# PokerFaceTestBoard.net
KiCad netlist of a schematic drawn in Altium Designer
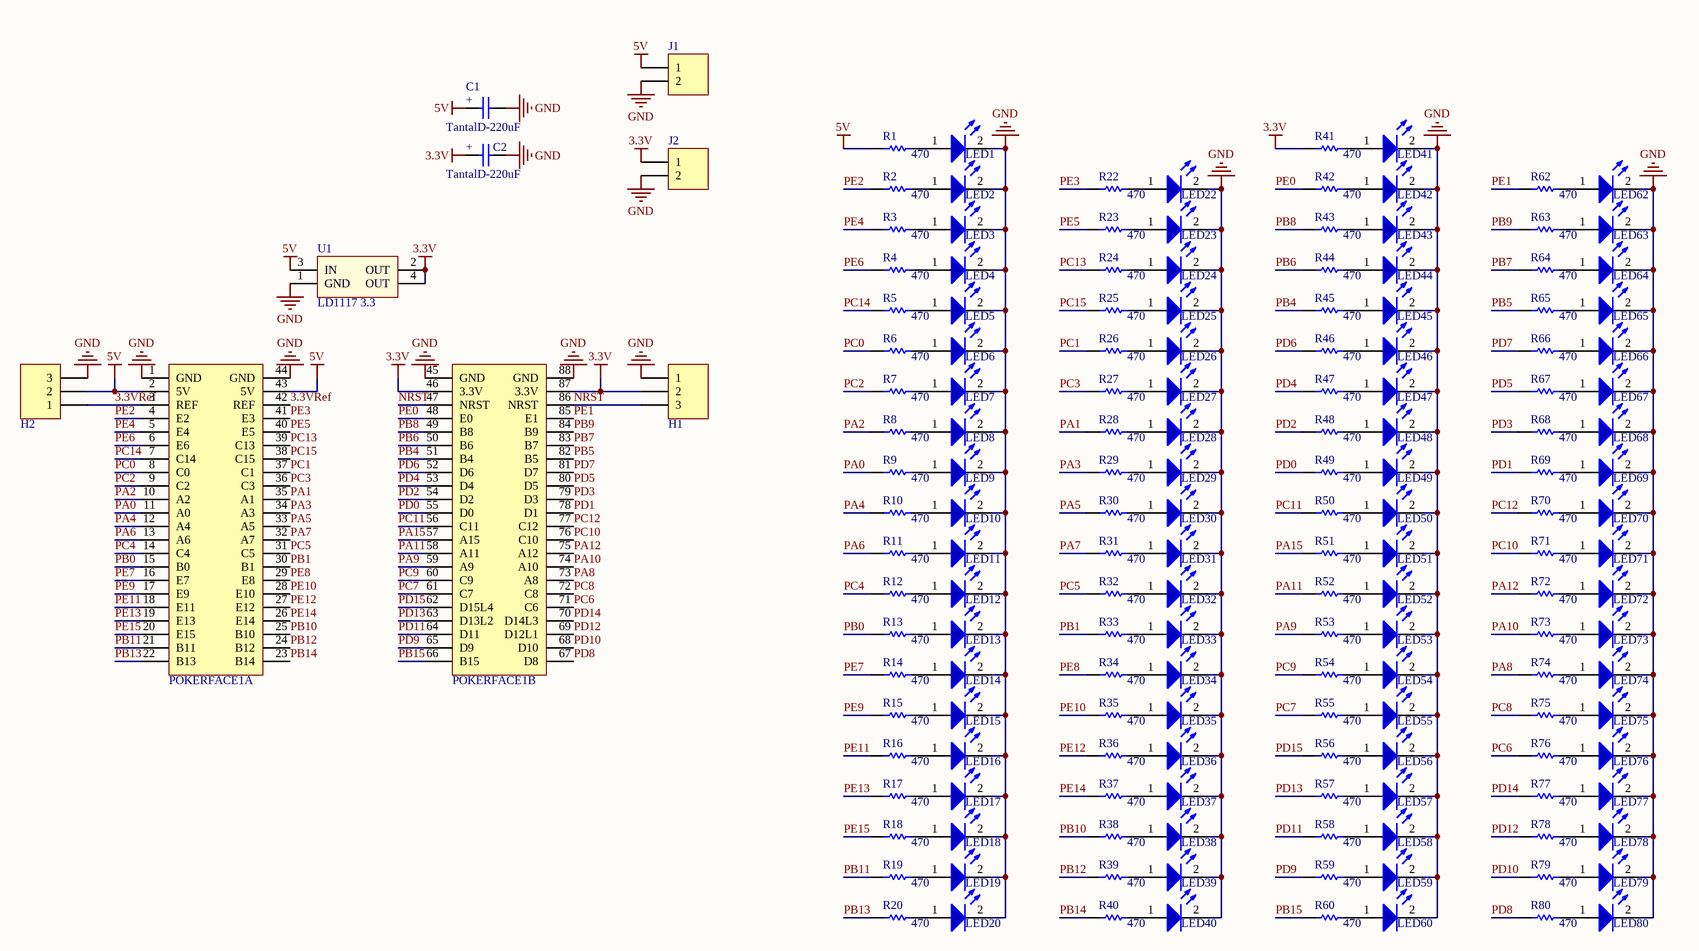
[diagram p0: PokerFaceTestBoard.SchDoc]

(export (version "E")
  (design (tool "Eeschema 10.0.6"))
  (components
    (comp (ref "C1")
      (value "TantalD-220uF")
      (footprint "MY_CAP_SMD-D")
      (description "7.3X4.3MM")
      (libsource (lib "AMINLIB") (part "CAP_TANTAL_D"))
    )
    (comp (ref "C2")
      (value "TantalD-220uF")
      (footprint "MY_CAP_SMD-D")
      (description "7.3X4.3MM")
      (libsource (lib "AMINLIB") (part "CAP_TANTAL_D"))
    )
    (comp (ref "H1")
      (value "WE-2.54 mm Pin Header & Jumper 61300311121")
      (footprint "61300311121")
      (description "WR-PHD 2.54mm Pin Header")
      (fields
        (field (name "MANUFACTURER") "Würth Elektronik eiSos GmbH")
        (field (name "PARTNO") "61300311121")
        (field (name "CREATED BY") "Karrer Zheng")
      )
      (libsource (lib "") (part "WE-2.54 mm Pin Header & Jumper 61300311121_1"))
    )
    (comp (ref "H2")
      (value "WE-2.54 mm Pin Header & Jumper 61300311121")
      (footprint "61300311121")
      (description "WR-PHD 2.54mm Pin Header")
      (fields
        (field (name "MANUFACTURER") "Würth Elektronik eiSos GmbH")
        (field (name "PARTNO") "61300311121")
        (field (name "CREATED BY") "Karrer Zheng")
      )
      (libsource (lib "WE_WR-PHD_Pin Header_2.54mm_rev15c") (part "WE-2.54 mm Pin Header & Jumper 61300311121"))
    )
    (comp (ref "J1")
      (value "691312510002")
      (footprint "691312510002")
      (description "WR-TBL Terminal Blocks Serie 312 – 5.08 mm")
      (fields
        (field (name "MANUFACTURER") "Würth Elektronik eiSos GmbH")
        (field (name "CREATED BY") "Karrer Zheng")
      )
      (libsource (lib "WE_WR-TBL_Pluggable System_5.08 mm_rev15b") (part "691312510002"))
    )
    (comp (ref "J2")
      (value "691312510002")
      (footprint "691312510002")
      (description "WR-TBL Terminal Blocks Serie 312 – 5.08 mm")
      (fields
        (field (name "MANUFACTURER") "Würth Elektronik eiSos GmbH")
        (field (name "CREATED BY") "Karrer Zheng")
      )
      (libsource (lib "WE_WR-TBL_Pluggable System_5.08 mm_rev15b") (part "691312510002"))
    )
    (comp (ref "LED1")
      (value "150080BS75000")
      (footprint "LED_0805_Blue")
      (description "SMD mono-color Chip LED, WL-SMCW, Blue")
      (fields
        (field (name "MANUFACTURER") "W黵th Elektronik eiSos GmbH")
        (field (name "CREATED BY") "Christin Otto")
      )
      (libsource (lib "WL-SMCW_rev15b1") (part "WL-SMCW 0805  150080BS75000"))
    )
    (comp (ref "LED2")
      (value "150080BS75000")
      (footprint "LED_0805_Blue")
      (description "SMD mono-color Chip LED, WL-SMCW, Blue")
      (fields
        (field (name "MANUFACTURER") "W黵th Elektronik eiSos GmbH")
        (field (name "CREATED BY") "Christin Otto")
      )
      (libsource (lib "WL-SMCW_rev15b1") (part "WL-SMCW 0805  150080BS75000"))
    )
    (comp (ref "LED3")
      (value "150080BS75000")
      (footprint "LED_0805_Blue")
      (description "SMD mono-color Chip LED, WL-SMCW, Blue")
      (fields
        (field (name "MANUFACTURER") "W黵th Elektronik eiSos GmbH")
        (field (name "CREATED BY") "Christin Otto")
      )
      (libsource (lib "WL-SMCW_rev15b1") (part "WL-SMCW 0805  150080BS75000"))
    )
    (comp (ref "LED4")
      (value "150080BS75000")
      (footprint "LED_0805_Blue")
      (description "SMD mono-color Chip LED, WL-SMCW, Blue")
      (fields
        (field (name "MANUFACTURER") "W黵th Elektronik eiSos GmbH")
        (field (name "CREATED BY") "Christin Otto")
      )
      (libsource (lib "WL-SMCW_rev15b1") (part "WL-SMCW 0805  150080BS75000"))
    )
    (comp (ref "LED5")
      (value "150080BS75000")
      (footprint "LED_0805_Blue")
      (description "SMD mono-color Chip LED, WL-SMCW, Blue")
      (fields
        (field (name "MANUFACTURER") "W黵th Elektronik eiSos GmbH")
        (field (name "CREATED BY") "Christin Otto")
      )
      (libsource (lib "WL-SMCW_rev15b1") (part "WL-SMCW 0805  150080BS75000"))
    )
    (comp (ref "LED6")
      (value "150080BS75000")
      (footprint "LED_0805_Blue")
      (description "SMD mono-color Chip LED, WL-SMCW, Blue")
      (fields
        (field (name "MANUFACTURER") "W黵th Elektronik eiSos GmbH")
        (field (name "CREATED BY") "Christin Otto")
      )
      (libsource (lib "WL-SMCW_rev15b1") (part "WL-SMCW 0805  150080BS75000"))
    )
    (comp (ref "LED7")
      (value "150080BS75000")
      (footprint "LED_0805_Blue")
      (description "SMD mono-color Chip LED, WL-SMCW, Blue")
      (fields
        (field (name "MANUFACTURER") "W黵th Elektronik eiSos GmbH")
        (field (name "CREATED BY") "Christin Otto")
      )
      (libsource (lib "WL-SMCW_rev15b1") (part "WL-SMCW 0805  150080BS75000"))
    )
    (comp (ref "LED8")
      (value "150080BS75000")
      (footprint "LED_0805_Blue")
      (description "SMD mono-color Chip LED, WL-SMCW, Blue")
      (fields
        (field (name "MANUFACTURER") "W黵th Elektronik eiSos GmbH")
        (field (name "CREATED BY") "Christin Otto")
      )
      (libsource (lib "WL-SMCW_rev15b1") (part "WL-SMCW 0805  150080BS75000"))
    )
    (comp (ref "LED9")
      (value "150080BS75000")
      (footprint "LED_0805_Blue")
      (description "SMD mono-color Chip LED, WL-SMCW, Blue")
      (fields
        (field (name "MANUFACTURER") "W黵th Elektronik eiSos GmbH")
        (field (name "CREATED BY") "Christin Otto")
      )
      (libsource (lib "WL-SMCW_rev15b1") (part "WL-SMCW 0805  150080BS75000"))
    )
    (comp (ref "LED10")
      (value "150080BS75000")
      (footprint "LED_0805_Blue")
      (description "SMD mono-color Chip LED, WL-SMCW, Blue")
      (fields
        (field (name "MANUFACTURER") "W黵th Elektronik eiSos GmbH")
        (field (name "CREATED BY") "Christin Otto")
      )
      (libsource (lib "WL-SMCW_rev15b1") (part "WL-SMCW 0805  150080BS75000"))
    )
    (comp (ref "LED11")
      (value "150080BS75000")
      (footprint "LED_0805_Blue")
      (description "SMD mono-color Chip LED, WL-SMCW, Blue")
      (fields
        (field (name "MANUFACTURER") "W黵th Elektronik eiSos GmbH")
        (field (name "CREATED BY") "Christin Otto")
      )
      (libsource (lib "WL-SMCW_rev15b1") (part "WL-SMCW 0805  150080BS75000"))
    )
    (comp (ref "LED12")
      (value "150080BS75000")
      (footprint "LED_0805_Blue")
      (description "SMD mono-color Chip LED, WL-SMCW, Blue")
      (fields
        (field (name "MANUFACTURER") "W黵th Elektronik eiSos GmbH")
        (field (name "CREATED BY") "Christin Otto")
      )
      (libsource (lib "WL-SMCW_rev15b1") (part "WL-SMCW 0805  150080BS75000"))
    )
    (comp (ref "LED13")
      (value "150080BS75000")
      (footprint "LED_0805_Blue")
      (description "SMD mono-color Chip LED, WL-SMCW, Blue")
      (fields
        (field (name "MANUFACTURER") "W黵th Elektronik eiSos GmbH")
        (field (name "CREATED BY") "Christin Otto")
      )
      (libsource (lib "WL-SMCW_rev15b1") (part "WL-SMCW 0805  150080BS75000"))
    )
    (comp (ref "LED14")
      (value "150080BS75000")
      (footprint "LED_0805_Blue")
      (description "SMD mono-color Chip LED, WL-SMCW, Blue")
      (fields
        (field (name "MANUFACTURER") "W黵th Elektronik eiSos GmbH")
        (field (name "CREATED BY") "Christin Otto")
      )
      (libsource (lib "WL-SMCW_rev15b1") (part "WL-SMCW 0805  150080BS75000"))
    )
    (comp (ref "LED15")
      (value "150080BS75000")
      (footprint "LED_0805_Blue")
      (description "SMD mono-color Chip LED, WL-SMCW, Blue")
      (fields
        (field (name "MANUFACTURER") "W黵th Elektronik eiSos GmbH")
        (field (name "CREATED BY") "Christin Otto")
      )
      (libsource (lib "WL-SMCW_rev15b1") (part "WL-SMCW 0805  150080BS75000"))
    )
    (comp (ref "LED16")
      (value "150080BS75000")
      (footprint "LED_0805_Blue")
      (description "SMD mono-color Chip LED, WL-SMCW, Blue")
      (fields
        (field (name "MANUFACTURER") "W黵th Elektronik eiSos GmbH")
        (field (name "CREATED BY") "Christin Otto")
      )
      (libsource (lib "WL-SMCW_rev15b1") (part "WL-SMCW 0805  150080BS75000"))
    )
    (comp (ref "LED17")
      (value "150080BS75000")
      (footprint "LED_0805_Blue")
      (description "SMD mono-color Chip LED, WL-SMCW, Blue")
      (fields
        (field (name "MANUFACTURER") "W黵th Elektronik eiSos GmbH")
        (field (name "CREATED BY") "Christin Otto")
      )
      (libsource (lib "WL-SMCW_rev15b1") (part "WL-SMCW 0805  150080BS75000"))
    )
    (comp (ref "LED18")
      (value "150080BS75000")
      (footprint "LED_0805_Blue")
      (description "SMD mono-color Chip LED, WL-SMCW, Blue")
      (fields
        (field (name "MANUFACTURER") "W黵th Elektronik eiSos GmbH")
        (field (name "CREATED BY") "Christin Otto")
      )
      (libsource (lib "WL-SMCW_rev15b1") (part "WL-SMCW 0805  150080BS75000"))
    )
    (comp (ref "LED19")
      (value "150080BS75000")
      (footprint "LED_0805_Blue")
      (description "SMD mono-color Chip LED, WL-SMCW, Blue")
      (fields
        (field (name "MANUFACTURER") "W黵th Elektronik eiSos GmbH")
        (field (name "CREATED BY") "Christin Otto")
      )
      (libsource (lib "WL-SMCW_rev15b1") (part "WL-SMCW 0805  150080BS75000"))
    )
    (comp (ref "LED20")
      (value "150080BS75000")
      (footprint "LED_0805_Blue")
      (description "SMD mono-color Chip LED, WL-SMCW, Blue")
      (fields
        (field (name "MANUFACTURER") "W黵th Elektronik eiSos GmbH")
        (field (name "CREATED BY") "Christin Otto")
      )
      (libsource (lib "WL-SMCW_rev15b1") (part "WL-SMCW 0805  150080BS75000"))
    )
    (comp (ref "LED22")
      (value "150080BS75000")
      (footprint "LED_0805_Blue")
      (description "SMD mono-color Chip LED, WL-SMCW, Blue")
      (fields
        (field (name "MANUFACTURER") "W黵th Elektronik eiSos GmbH")
        (field (name "CREATED BY") "Christin Otto")
      )
      (libsource (lib "WL-SMCW_rev15b1") (part "WL-SMCW 0805  150080BS75000"))
    )
    (comp (ref "LED23")
      (value "150080BS75000")
      (footprint "LED_0805_Blue")
      (description "SMD mono-color Chip LED, WL-SMCW, Blue")
      (fields
        (field (name "MANUFACTURER") "W黵th Elektronik eiSos GmbH")
        (field (name "CREATED BY") "Christin Otto")
      )
      (libsource (lib "WL-SMCW_rev15b1") (part "WL-SMCW 0805  150080BS75000"))
    )
    (comp (ref "LED24")
      (value "150080BS75000")
      (footprint "LED_0805_Blue")
      (description "SMD mono-color Chip LED, WL-SMCW, Blue")
      (fields
        (field (name "MANUFACTURER") "W黵th Elektronik eiSos GmbH")
        (field (name "CREATED BY") "Christin Otto")
      )
      (libsource (lib "WL-SMCW_rev15b1") (part "WL-SMCW 0805  150080BS75000"))
    )
    (comp (ref "LED25")
      (value "150080BS75000")
      (footprint "LED_0805_Blue")
      (description "SMD mono-color Chip LED, WL-SMCW, Blue")
      (fields
        (field (name "MANUFACTURER") "W黵th Elektronik eiSos GmbH")
        (field (name "CREATED BY") "Christin Otto")
      )
      (libsource (lib "WL-SMCW_rev15b1") (part "WL-SMCW 0805  150080BS75000"))
    )
    (comp (ref "LED26")
      (value "150080BS75000")
      (footprint "LED_0805_Blue")
      (description "SMD mono-color Chip LED, WL-SMCW, Blue")
      (fields
        (field (name "MANUFACTURER") "W黵th Elektronik eiSos GmbH")
        (field (name "CREATED BY") "Christin Otto")
      )
      (libsource (lib "WL-SMCW_rev15b1") (part "WL-SMCW 0805  150080BS75000"))
    )
    (comp (ref "LED27")
      (value "150080BS75000")
      (footprint "LED_0805_Blue")
      (description "SMD mono-color Chip LED, WL-SMCW, Blue")
      (fields
        (field (name "MANUFACTURER") "W黵th Elektronik eiSos GmbH")
        (field (name "CREATED BY") "Christin Otto")
      )
      (libsource (lib "WL-SMCW_rev15b1") (part "WL-SMCW 0805  150080BS75000"))
    )
    (comp (ref "LED28")
      (value "150080BS75000")
      (footprint "LED_0805_Blue")
      (description "SMD mono-color Chip LED, WL-SMCW, Blue")
      (fields
        (field (name "MANUFACTURER") "W黵th Elektronik eiSos GmbH")
        (field (name "CREATED BY") "Christin Otto")
      )
      (libsource (lib "WL-SMCW_rev15b1") (part "WL-SMCW 0805  150080BS75000"))
    )
    (comp (ref "LED29")
      (value "150080BS75000")
      (footprint "LED_0805_Blue")
      (description "SMD mono-color Chip LED, WL-SMCW, Blue")
      (fields
        (field (name "MANUFACTURER") "W黵th Elektronik eiSos GmbH")
        (field (name "CREATED BY") "Christin Otto")
      )
      (libsource (lib "WL-SMCW_rev15b1") (part "WL-SMCW 0805  150080BS75000"))
    )
    (comp (ref "LED30")
      (value "150080BS75000")
      (footprint "LED_0805_Blue")
      (description "SMD mono-color Chip LED, WL-SMCW, Blue")
      (fields
        (field (name "MANUFACTURER") "W黵th Elektronik eiSos GmbH")
        (field (name "CREATED BY") "Christin Otto")
      )
      (libsource (lib "WL-SMCW_rev15b1") (part "WL-SMCW 0805  150080BS75000"))
    )
    (comp (ref "LED31")
      (value "150080BS75000")
      (footprint "LED_0805_Blue")
      (description "SMD mono-color Chip LED, WL-SMCW, Blue")
      (fields
        (field (name "MANUFACTURER") "W黵th Elektronik eiSos GmbH")
        (field (name "CREATED BY") "Christin Otto")
      )
      (libsource (lib "WL-SMCW_rev15b1") (part "WL-SMCW 0805  150080BS75000"))
    )
    (comp (ref "LED32")
      (value "150080BS75000")
      (footprint "LED_0805_Blue")
      (description "SMD mono-color Chip LED, WL-SMCW, Blue")
      (fields
        (field (name "MANUFACTURER") "W黵th Elektronik eiSos GmbH")
        (field (name "CREATED BY") "Christin Otto")
      )
      (libsource (lib "WL-SMCW_rev15b1") (part "WL-SMCW 0805  150080BS75000"))
    )
    (comp (ref "LED33")
      (value "150080BS75000")
      (footprint "LED_0805_Blue")
      (description "SMD mono-color Chip LED, WL-SMCW, Blue")
      (fields
        (field (name "MANUFACTURER") "W黵th Elektronik eiSos GmbH")
        (field (name "CREATED BY") "Christin Otto")
      )
      (libsource (lib "WL-SMCW_rev15b1") (part "WL-SMCW 0805  150080BS75000"))
    )
    (comp (ref "LED34")
      (value "150080BS75000")
      (footprint "LED_0805_Blue")
      (description "SMD mono-color Chip LED, WL-SMCW, Blue")
      (fields
        (field (name "MANUFACTURER") "W黵th Elektronik eiSos GmbH")
        (field (name "CREATED BY") "Christin Otto")
      )
      (libsource (lib "WL-SMCW_rev15b1") (part "WL-SMCW 0805  150080BS75000"))
    )
    (comp (ref "LED35")
      (value "150080BS75000")
      (footprint "LED_0805_Blue")
      (description "SMD mono-color Chip LED, WL-SMCW, Blue")
      (fields
        (field (name "MANUFACTURER") "W黵th Elektronik eiSos GmbH")
        (field (name "CREATED BY") "Christin Otto")
      )
      (libsource (lib "WL-SMCW_rev15b1") (part "WL-SMCW 0805  150080BS75000"))
    )
    (comp (ref "LED36")
      (value "150080BS75000")
      (footprint "LED_0805_Blue")
      (description "SMD mono-color Chip LED, WL-SMCW, Blue")
      (fields
        (field (name "MANUFACTURER") "W黵th Elektronik eiSos GmbH")
        (field (name "CREATED BY") "Christin Otto")
      )
      (libsource (lib "WL-SMCW_rev15b1") (part "WL-SMCW 0805  150080BS75000"))
    )
    (comp (ref "LED37")
      (value "150080BS75000")
      (footprint "LED_0805_Blue")
      (description "SMD mono-color Chip LED, WL-SMCW, Blue")
      (fields
        (field (name "MANUFACTURER") "W黵th Elektronik eiSos GmbH")
        (field (name "CREATED BY") "Christin Otto")
      )
      (libsource (lib "WL-SMCW_rev15b1") (part "WL-SMCW 0805  150080BS75000"))
    )
    (comp (ref "LED38")
      (value "150080BS75000")
      (footprint "LED_0805_Blue")
      (description "SMD mono-color Chip LED, WL-SMCW, Blue")
      (fields
        (field (name "MANUFACTURER") "W黵th Elektronik eiSos GmbH")
        (field (name "CREATED BY") "Christin Otto")
      )
      (libsource (lib "WL-SMCW_rev15b1") (part "WL-SMCW 0805  150080BS75000"))
    )
    (comp (ref "LED39")
      (value "150080BS75000")
      (footprint "LED_0805_Blue")
      (description "SMD mono-color Chip LED, WL-SMCW, Blue")
      (fields
        (field (name "MANUFACTURER") "W黵th Elektronik eiSos GmbH")
        (field (name "CREATED BY") "Christin Otto")
      )
      (libsource (lib "WL-SMCW_rev15b1") (part "WL-SMCW 0805  150080BS75000"))
    )
    (comp (ref "LED40")
      (value "150080BS75000")
      (footprint "LED_0805_Blue")
      (description "SMD mono-color Chip LED, WL-SMCW, Blue")
      (fields
        (field (name "MANUFACTURER") "W黵th Elektronik eiSos GmbH")
        (field (name "CREATED BY") "Christin Otto")
      )
      (libsource (lib "WL-SMCW_rev15b1") (part "WL-SMCW 0805  150080BS75000"))
    )
    (comp (ref "LED41")
      (value "150080BS75000")
      (footprint "LED_0805_Blue")
      (description "SMD mono-color Chip LED, WL-SMCW, Blue")
      (fields
        (field (name "MANUFACTURER") "W黵th Elektronik eiSos GmbH")
        (field (name "CREATED BY") "Christin Otto")
      )
      (libsource (lib "WL-SMCW_rev15b1") (part "WL-SMCW 0805  150080BS75000"))
    )
    (comp (ref "LED42")
      (value "150080BS75000")
      (footprint "LED_0805_Blue")
      (description "SMD mono-color Chip LED, WL-SMCW, Blue")
      (fields
        (field (name "MANUFACTURER") "W黵th Elektronik eiSos GmbH")
        (field (name "CREATED BY") "Christin Otto")
      )
      (libsource (lib "WL-SMCW_rev15b1") (part "WL-SMCW 0805  150080BS75000"))
    )
    (comp (ref "LED43")
      (value "150080BS75000")
      (footprint "LED_0805_Blue")
      (description "SMD mono-color Chip LED, WL-SMCW, Blue")
      (fields
        (field (name "MANUFACTURER") "W黵th Elektronik eiSos GmbH")
        (field (name "CREATED BY") "Christin Otto")
      )
      (libsource (lib "WL-SMCW_rev15b1") (part "WL-SMCW 0805  150080BS75000"))
    )
    (comp (ref "LED44")
      (value "150080BS75000")
      (footprint "LED_0805_Blue")
      (description "SMD mono-color Chip LED, WL-SMCW, Blue")
      (fields
        (field (name "MANUFACTURER") "W黵th Elektronik eiSos GmbH")
        (field (name "CREATED BY") "Christin Otto")
      )
      (libsource (lib "WL-SMCW_rev15b1") (part "WL-SMCW 0805  150080BS75000"))
    )
    (comp (ref "LED45")
      (value "150080BS75000")
      (footprint "LED_0805_Blue")
      (description "SMD mono-color Chip LED, WL-SMCW, Blue")
      (fields
        (field (name "MANUFACTURER") "W黵th Elektronik eiSos GmbH")
        (field (name "CREATED BY") "Christin Otto")
      )
      (libsource (lib "WL-SMCW_rev15b1") (part "WL-SMCW 0805  150080BS75000"))
    )
    (comp (ref "LED46")
      (value "150080BS75000")
      (footprint "LED_0805_Blue")
      (description "SMD mono-color Chip LED, WL-SMCW, Blue")
      (fields
        (field (name "MANUFACTURER") "W黵th Elektronik eiSos GmbH")
        (field (name "CREATED BY") "Christin Otto")
      )
      (libsource (lib "WL-SMCW_rev15b1") (part "WL-SMCW 0805  150080BS75000"))
    )
    (comp (ref "LED47")
      (value "150080BS75000")
      (footprint "LED_0805_Blue")
      (description "SMD mono-color Chip LED, WL-SMCW, Blue")
      (fields
        (field (name "MANUFACTURER") "W黵th Elektronik eiSos GmbH")
        (field (name "CREATED BY") "Christin Otto")
      )
      (libsource (lib "WL-SMCW_rev15b1") (part "WL-SMCW 0805  150080BS75000"))
    )
    (comp (ref "LED48")
      (value "150080BS75000")
      (footprint "LED_0805_Blue")
      (description "SMD mono-color Chip LED, WL-SMCW, Blue")
      (fields
        (field (name "MANUFACTURER") "W黵th Elektronik eiSos GmbH")
        (field (name "CREATED BY") "Christin Otto")
      )
      (libsource (lib "WL-SMCW_rev15b1") (part "WL-SMCW 0805  150080BS75000"))
    )
    (comp (ref "LED49")
      (value "150080BS75000")
      (footprint "LED_0805_Blue")
      (description "SMD mono-color Chip LED, WL-SMCW, Blue")
      (fields
        (field (name "MANUFACTURER") "W黵th Elektronik eiSos GmbH")
        (field (name "CREATED BY") "Christin Otto")
      )
      (libsource (lib "WL-SMCW_rev15b1") (part "WL-SMCW 0805  150080BS75000"))
    )
    (comp (ref "LED50")
      (value "150080BS75000")
      (footprint "LED_0805_Blue")
      (description "SMD mono-color Chip LED, WL-SMCW, Blue")
      (fields
        (field (name "MANUFACTURER") "W黵th Elektronik eiSos GmbH")
        (field (name "CREATED BY") "Christin Otto")
      )
      (libsource (lib "WL-SMCW_rev15b1") (part "WL-SMCW 0805  150080BS75000"))
    )
    (comp (ref "LED51")
      (value "150080BS75000")
      (footprint "LED_0805_Blue")
      (description "SMD mono-color Chip LED, WL-SMCW, Blue")
      (fields
        (field (name "MANUFACTURER") "W黵th Elektronik eiSos GmbH")
        (field (name "CREATED BY") "Christin Otto")
      )
      (libsource (lib "WL-SMCW_rev15b1") (part "WL-SMCW 0805  150080BS75000"))
    )
    (comp (ref "LED52")
      (value "150080BS75000")
      (footprint "LED_0805_Blue")
      (description "SMD mono-color Chip LED, WL-SMCW, Blue")
      (fields
        (field (name "MANUFACTURER") "W黵th Elektronik eiSos GmbH")
        (field (name "CREATED BY") "Christin Otto")
      )
      (libsource (lib "WL-SMCW_rev15b1") (part "WL-SMCW 0805  150080BS75000"))
    )
    (comp (ref "LED53")
      (value "150080BS75000")
      (footprint "LED_0805_Blue")
      (description "SMD mono-color Chip LED, WL-SMCW, Blue")
      (fields
        (field (name "MANUFACTURER") "W黵th Elektronik eiSos GmbH")
        (field (name "CREATED BY") "Christin Otto")
      )
      (libsource (lib "WL-SMCW_rev15b1") (part "WL-SMCW 0805  150080BS75000"))
    )
    (comp (ref "LED54")
      (value "150080BS75000")
      (footprint "LED_0805_Blue")
      (description "SMD mono-color Chip LED, WL-SMCW, Blue")
      (fields
        (field (name "MANUFACTURER") "W黵th Elektronik eiSos GmbH")
        (field (name "CREATED BY") "Christin Otto")
      )
      (libsource (lib "WL-SMCW_rev15b1") (part "WL-SMCW 0805  150080BS75000"))
    )
    (comp (ref "LED55")
      (value "150080BS75000")
      (footprint "LED_0805_Blue")
      (description "SMD mono-color Chip LED, WL-SMCW, Blue")
      (fields
        (field (name "MANUFACTURER") "W黵th Elektronik eiSos GmbH")
        (field (name "CREATED BY") "Christin Otto")
      )
      (libsource (lib "WL-SMCW_rev15b1") (part "WL-SMCW 0805  150080BS75000"))
    )
    (comp (ref "LED56")
      (value "150080BS75000")
      (footprint "LED_0805_Blue")
      (description "SMD mono-color Chip LED, WL-SMCW, Blue")
      (fields
        (field (name "MANUFACTURER") "W黵th Elektronik eiSos GmbH")
        (field (name "CREATED BY") "Christin Otto")
      )
      (libsource (lib "WL-SMCW_rev15b1") (part "WL-SMCW 0805  150080BS75000"))
    )
    (comp (ref "LED57")
      (value "150080BS75000")
      (footprint "LED_0805_Blue")
      (description "SMD mono-color Chip LED, WL-SMCW, Blue")
      (fields
        (field (name "MANUFACTURER") "W黵th Elektronik eiSos GmbH")
        (field (name "CREATED BY") "Christin Otto")
      )
      (libsource (lib "WL-SMCW_rev15b1") (part "WL-SMCW 0805  150080BS75000"))
    )
    (comp (ref "LED58")
      (value "150080BS75000")
      (footprint "LED_0805_Blue")
      (description "SMD mono-color Chip LED, WL-SMCW, Blue")
      (fields
        (field (name "MANUFACTURER") "W黵th Elektronik eiSos GmbH")
        (field (name "CREATED BY") "Christin Otto")
      )
      (libsource (lib "WL-SMCW_rev15b1") (part "WL-SMCW 0805  150080BS75000"))
    )
    (comp (ref "LED59")
      (value "150080BS75000")
      (footprint "LED_0805_Blue")
      (description "SMD mono-color Chip LED, WL-SMCW, Blue")
      (fields
        (field (name "MANUFACTURER") "W黵th Elektronik eiSos GmbH")
        (field (name "CREATED BY") "Christin Otto")
      )
      (libsource (lib "WL-SMCW_rev15b1") (part "WL-SMCW 0805  150080BS75000"))
    )
    (comp (ref "LED60")
      (value "150080BS75000")
      (footprint "LED_0805_Blue")
      (description "SMD mono-color Chip LED, WL-SMCW, Blue")
      (fields
        (field (name "MANUFACTURER") "W黵th Elektronik eiSos GmbH")
        (field (name "CREATED BY") "Christin Otto")
      )
      (libsource (lib "WL-SMCW_rev15b1") (part "WL-SMCW 0805  150080BS75000"))
    )
    (comp (ref "LED62")
      (value "150080BS75000")
      (footprint "LED_0805_Blue")
      (description "SMD mono-color Chip LED, WL-SMCW, Blue")
      (fields
        (field (name "MANUFACTURER") "W黵th Elektronik eiSos GmbH")
        (field (name "CREATED BY") "Christin Otto")
      )
      (libsource (lib "WL-SMCW_rev15b1") (part "WL-SMCW 0805  150080BS75000"))
    )
    (comp (ref "LED63")
      (value "150080BS75000")
      (footprint "LED_0805_Blue")
      (description "SMD mono-color Chip LED, WL-SMCW, Blue")
      (fields
        (field (name "MANUFACTURER") "W黵th Elektronik eiSos GmbH")
        (field (name "CREATED BY") "Christin Otto")
      )
      (libsource (lib "WL-SMCW_rev15b1") (part "WL-SMCW 0805  150080BS75000"))
    )
    (comp (ref "LED64")
      (value "150080BS75000")
      (footprint "LED_0805_Blue")
      (description "SMD mono-color Chip LED, WL-SMCW, Blue")
      (fields
        (field (name "MANUFACTURER") "W黵th Elektronik eiSos GmbH")
        (field (name "CREATED BY") "Christin Otto")
      )
      (libsource (lib "WL-SMCW_rev15b1") (part "WL-SMCW 0805  150080BS75000"))
    )
    (comp (ref "LED65")
      (value "150080BS75000")
      (footprint "LED_0805_Blue")
      (description "SMD mono-color Chip LED, WL-SMCW, Blue")
      (fields
        (field (name "MANUFACTURER") "W黵th Elektronik eiSos GmbH")
        (field (name "CREATED BY") "Christin Otto")
      )
      (libsource (lib "WL-SMCW_rev15b1") (part "WL-SMCW 0805  150080BS75000"))
    )
    (comp (ref "LED66")
      (value "150080BS75000")
      (footprint "LED_0805_Blue")
      (description "SMD mono-color Chip LED, WL-SMCW, Blue")
      (fields
        (field (name "MANUFACTURER") "W黵th Elektronik eiSos GmbH")
        (field (name "CREATED BY") "Christin Otto")
      )
      (libsource (lib "WL-SMCW_rev15b1") (part "WL-SMCW 0805  150080BS75000"))
    )
    (comp (ref "LED67")
      (value "150080BS75000")
      (footprint "LED_0805_Blue")
      (description "SMD mono-color Chip LED, WL-SMCW, Blue")
      (fields
        (field (name "MANUFACTURER") "W黵th Elektronik eiSos GmbH")
        (field (name "CREATED BY") "Christin Otto")
      )
      (libsource (lib "WL-SMCW_rev15b1") (part "WL-SMCW 0805  150080BS75000"))
    )
    (comp (ref "LED68")
      (value "150080BS75000")
      (footprint "LED_0805_Blue")
      (description "SMD mono-color Chip LED, WL-SMCW, Blue")
      (fields
        (field (name "MANUFACTURER") "W黵th Elektronik eiSos GmbH")
        (field (name "CREATED BY") "Christin Otto")
      )
      (libsource (lib "WL-SMCW_rev15b1") (part "WL-SMCW 0805  150080BS75000"))
    )
    (comp (ref "LED69")
      (value "150080BS75000")
      (footprint "LED_0805_Blue")
      (description "SMD mono-color Chip LED, WL-SMCW, Blue")
      (fields
        (field (name "MANUFACTURER") "W黵th Elektronik eiSos GmbH")
        (field (name "CREATED BY") "Christin Otto")
      )
      (libsource (lib "WL-SMCW_rev15b1") (part "WL-SMCW 0805  150080BS75000"))
    )
    (comp (ref "LED70")
      (value "150080BS75000")
      (footprint "LED_0805_Blue")
      (description "SMD mono-color Chip LED, WL-SMCW, Blue")
      (fields
        (field (name "MANUFACTURER") "W黵th Elektronik eiSos GmbH")
        (field (name "CREATED BY") "Christin Otto")
      )
      (libsource (lib "WL-SMCW_rev15b1") (part "WL-SMCW 0805  150080BS75000"))
    )
    (comp (ref "LED71")
      (value "150080BS75000")
      (footprint "LED_0805_Blue")
      (description "SMD mono-color Chip LED, WL-SMCW, Blue")
      (fields
        (field (name "MANUFACTURER") "W黵th Elektronik eiSos GmbH")
        (field (name "CREATED BY") "Christin Otto")
      )
      (libsource (lib "WL-SMCW_rev15b1") (part "WL-SMCW 0805  150080BS75000"))
    )
    (comp (ref "LED72")
      (value "150080BS75000")
      (footprint "LED_0805_Blue")
      (description "SMD mono-color Chip LED, WL-SMCW, Blue")
      (fields
        (field (name "MANUFACTURER") "W黵th Elektronik eiSos GmbH")
        (field (name "CREATED BY") "Christin Otto")
      )
      (libsource (lib "WL-SMCW_rev15b1") (part "WL-SMCW 0805  150080BS75000"))
    )
    (comp (ref "LED73")
      (value "150080BS75000")
      (footprint "LED_0805_Blue")
      (description "SMD mono-color Chip LED, WL-SMCW, Blue")
      (fields
        (field (name "MANUFACTURER") "W黵th Elektronik eiSos GmbH")
        (field (name "CREATED BY") "Christin Otto")
      )
      (libsource (lib "WL-SMCW_rev15b1") (part "WL-SMCW 0805  150080BS75000"))
    )
    (comp (ref "LED74")
      (value "150080BS75000")
      (footprint "LED_0805_Blue")
      (description "SMD mono-color Chip LED, WL-SMCW, Blue")
      (fields
        (field (name "MANUFACTURER") "W黵th Elektronik eiSos GmbH")
        (field (name "CREATED BY") "Christin Otto")
      )
      (libsource (lib "WL-SMCW_rev15b1") (part "WL-SMCW 0805  150080BS75000"))
    )
    (comp (ref "LED75")
      (value "150080BS75000")
      (footprint "LED_0805_Blue")
      (description "SMD mono-color Chip LED, WL-SMCW, Blue")
      (fields
        (field (name "MANUFACTURER") "W黵th Elektronik eiSos GmbH")
        (field (name "CREATED BY") "Christin Otto")
      )
      (libsource (lib "WL-SMCW_rev15b1") (part "WL-SMCW 0805  150080BS75000"))
    )
    (comp (ref "LED76")
      (value "150080BS75000")
      (footprint "LED_0805_Blue")
      (description "SMD mono-color Chip LED, WL-SMCW, Blue")
      (fields
        (field (name "MANUFACTURER") "W黵th Elektronik eiSos GmbH")
        (field (name "CREATED BY") "Christin Otto")
      )
      (libsource (lib "WL-SMCW_rev15b1") (part "WL-SMCW 0805  150080BS75000"))
    )
    (comp (ref "LED77")
      (value "150080BS75000")
      (footprint "LED_0805_Blue")
      (description "SMD mono-color Chip LED, WL-SMCW, Blue")
      (fields
        (field (name "MANUFACTURER") "W黵th Elektronik eiSos GmbH")
        (field (name "CREATED BY") "Christin Otto")
      )
      (libsource (lib "WL-SMCW_rev15b1") (part "WL-SMCW 0805  150080BS75000"))
    )
    (comp (ref "LED78")
      (value "150080BS75000")
      (footprint "LED_0805_Blue")
      (description "SMD mono-color Chip LED, WL-SMCW, Blue")
      (fields
        (field (name "MANUFACTURER") "W黵th Elektronik eiSos GmbH")
        (field (name "CREATED BY") "Christin Otto")
      )
      (libsource (lib "WL-SMCW_rev15b1") (part "WL-SMCW 0805  150080BS75000"))
    )
    (comp (ref "LED79")
      (value "150080BS75000")
      (footprint "LED_0805_Blue")
      (description "SMD mono-color Chip LED, WL-SMCW, Blue")
      (fields
        (field (name "MANUFACTURER") "W黵th Elektronik eiSos GmbH")
        (field (name "CREATED BY") "Christin Otto")
      )
      (libsource (lib "WL-SMCW_rev15b1") (part "WL-SMCW 0805  150080BS75000"))
    )
    (comp (ref "LED80")
      (value "150080BS75000")
      (footprint "LED_0805_Blue")
      (description "SMD mono-color Chip LED, WL-SMCW, Blue")
      (fields
        (field (name "MANUFACTURER") "W黵th Elektronik eiSos GmbH")
        (field (name "CREATED BY") "Christin Otto")
      )
      (libsource (lib "WL-SMCW_rev15b1") (part "WL-SMCW 0805  150080BS75000"))
    )
    (comp (ref "POKERFACE1")
      (value "POKERFACEV1-1")
      (footprint "PokerFaceV1-1")
      (libsource (lib "Aryalib") (part "POKERFACEV1-1"))
    )
    (comp (ref "R1") (value "470") (footprint "SMD 805") (libsource (lib "Aryalib") (part "Resistor")))
    (comp (ref "R2") (value "470") (footprint "SMD 805") (libsource (lib "Aryalib") (part "Resistor")))
    (comp (ref "R3") (value "470") (footprint "SMD 805") (libsource (lib "Aryalib") (part "Resistor")))
    (comp (ref "R4") (value "470") (footprint "SMD 805") (libsource (lib "Aryalib") (part "Resistor")))
    (comp (ref "R5") (value "470") (footprint "SMD 805") (libsource (lib "Aryalib") (part "Resistor")))
    (comp (ref "R6") (value "470") (footprint "SMD 805") (libsource (lib "Aryalib") (part "Resistor")))
    (comp (ref "R7") (value "470") (footprint "SMD 805") (libsource (lib "Aryalib") (part "Resistor")))
    (comp (ref "R8") (value "470") (footprint "SMD 805") (libsource (lib "Aryalib") (part "Resistor")))
    (comp (ref "R9") (value "470") (footprint "SMD 805") (libsource (lib "Aryalib") (part "Resistor")))
    (comp (ref "R10") (value "470") (footprint "SMD 805") (libsource (lib "Aryalib") (part "Resistor")))
    (comp (ref "R11") (value "470") (footprint "SMD 805") (libsource (lib "Aryalib") (part "Resistor")))
    (comp (ref "R12") (value "470") (footprint "SMD 805") (libsource (lib "Aryalib") (part "Resistor")))
    (comp (ref "R13") (value "470") (footprint "SMD 805") (libsource (lib "Aryalib") (part "Resistor")))
    (comp (ref "R14") (value "470") (footprint "SMD 805") (libsource (lib "Aryalib") (part "Resistor")))
    (comp (ref "R15") (value "470") (footprint "SMD 805") (libsource (lib "Aryalib") (part "Resistor")))
    (comp (ref "R16") (value "470") (footprint "SMD 805") (libsource (lib "Aryalib") (part "Resistor")))
    (comp (ref "R17") (value "470") (footprint "SMD 805") (libsource (lib "Aryalib") (part "Resistor")))
    (comp (ref "R18") (value "470") (footprint "SMD 805") (libsource (lib "Aryalib") (part "Resistor")))
    (comp (ref "R19") (value "470") (footprint "SMD 805") (libsource (lib "Aryalib") (part "Resistor")))
    (comp (ref "R20") (value "470") (footprint "SMD 805") (libsource (lib "Aryalib") (part "Resistor")))
    (comp (ref "R22") (value "470") (footprint "SMD 805") (libsource (lib "Aryalib") (part "Resistor")))
    (comp (ref "R23") (value "470") (footprint "SMD 805") (libsource (lib "Aryalib") (part "Resistor")))
    (comp (ref "R24") (value "470") (footprint "SMD 805") (libsource (lib "Aryalib") (part "Resistor")))
    (comp (ref "R25") (value "470") (footprint "SMD 805") (libsource (lib "Aryalib") (part "Resistor")))
    (comp (ref "R26") (value "470") (footprint "SMD 805") (libsource (lib "Aryalib") (part "Resistor")))
    (comp (ref "R27") (value "470") (footprint "SMD 805") (libsource (lib "Aryalib") (part "Resistor")))
    (comp (ref "R28") (value "470") (footprint "SMD 805") (libsource (lib "Aryalib") (part "Resistor")))
    (comp (ref "R29") (value "470") (footprint "SMD 805") (libsource (lib "Aryalib") (part "Resistor")))
    (comp (ref "R30") (value "470") (footprint "SMD 805") (libsource (lib "Aryalib") (part "Resistor")))
    (comp (ref "R31") (value "470") (footprint "SMD 805") (libsource (lib "Aryalib") (part "Resistor")))
    (comp (ref "R32") (value "470") (footprint "SMD 805") (libsource (lib "Aryalib") (part "Resistor")))
    (comp (ref "R33") (value "470") (footprint "SMD 805") (libsource (lib "Aryalib") (part "Resistor")))
    (comp (ref "R34") (value "470") (footprint "SMD 805") (libsource (lib "Aryalib") (part "Resistor")))
    (comp (ref "R35") (value "470") (footprint "SMD 805") (libsource (lib "Aryalib") (part "Resistor")))
    (comp (ref "R36") (value "470") (footprint "SMD 805") (libsource (lib "Aryalib") (part "Resistor")))
    (comp (ref "R37") (value "470") (footprint "SMD 805") (libsource (lib "Aryalib") (part "Resistor")))
    (comp (ref "R38") (value "470") (footprint "SMD 805") (libsource (lib "Aryalib") (part "Resistor")))
    (comp (ref "R39") (value "470") (footprint "SMD 805") (libsource (lib "Aryalib") (part "Resistor")))
    (comp (ref "R40") (value "470") (footprint "SMD 805") (libsource (lib "Aryalib") (part "Resistor")))
    (comp (ref "R41") (value "470") (footprint "SMD 805") (libsource (lib "Aryalib") (part "Resistor")))
    (comp (ref "R42") (value "470") (footprint "SMD 805") (libsource (lib "Aryalib") (part "Resistor")))
    (comp (ref "R43") (value "470") (footprint "SMD 805") (libsource (lib "Aryalib") (part "Resistor")))
    (comp (ref "R44") (value "470") (footprint "SMD 805") (libsource (lib "Aryalib") (part "Resistor")))
    (comp (ref "R45") (value "470") (footprint "SMD 805") (libsource (lib "Aryalib") (part "Resistor")))
    (comp (ref "R46") (value "470") (footprint "SMD 805") (libsource (lib "Aryalib") (part "Resistor")))
    (comp (ref "R47") (value "470") (footprint "SMD 805") (libsource (lib "Aryalib") (part "Resistor")))
    (comp (ref "R48") (value "470") (footprint "SMD 805") (libsource (lib "Aryalib") (part "Resistor")))
    (comp (ref "R49") (value "470") (footprint "SMD 805") (libsource (lib "Aryalib") (part "Resistor")))
    (comp (ref "R50") (value "470") (footprint "SMD 805") (libsource (lib "Aryalib") (part "Resistor")))
    (comp (ref "R51") (value "470") (footprint "SMD 805") (libsource (lib "Aryalib") (part "Resistor")))
    (comp (ref "R52") (value "470") (footprint "SMD 805") (libsource (lib "Aryalib") (part "Resistor")))
    (comp (ref "R53") (value "470") (footprint "SMD 805") (libsource (lib "Aryalib") (part "Resistor")))
    (comp (ref "R54") (value "470") (footprint "SMD 805") (libsource (lib "Aryalib") (part "Resistor")))
    (comp (ref "R55") (value "470") (footprint "SMD 805") (libsource (lib "Aryalib") (part "Resistor")))
    (comp (ref "R56") (value "470") (footprint "SMD 805") (libsource (lib "Aryalib") (part "Resistor")))
    (comp (ref "R57") (value "470") (footprint "SMD 805") (libsource (lib "Aryalib") (part "Resistor")))
    (comp (ref "R58") (value "470") (footprint "SMD 805") (libsource (lib "Aryalib") (part "Resistor")))
    (comp (ref "R59") (value "470") (footprint "SMD 805") (libsource (lib "Aryalib") (part "Resistor")))
    (comp (ref "R60") (value "470") (footprint "SMD 805") (libsource (lib "Aryalib") (part "Resistor")))
    (comp (ref "R62") (value "470") (footprint "SMD 805") (libsource (lib "Aryalib") (part "Resistor")))
    (comp (ref "R63") (value "470") (footprint "SMD 805") (libsource (lib "Aryalib") (part "Resistor")))
    (comp (ref "R64") (value "470") (footprint "SMD 805") (libsource (lib "Aryalib") (part "Resistor")))
    (comp (ref "R65") (value "470") (footprint "SMD 805") (libsource (lib "Aryalib") (part "Resistor")))
    (comp (ref "R66") (value "470") (footprint "SMD 805") (libsource (lib "Aryalib") (part "Resistor")))
    (comp (ref "R67") (value "470") (footprint "SMD 805") (libsource (lib "Aryalib") (part "Resistor")))
    (comp (ref "R68") (value "470") (footprint "SMD 805") (libsource (lib "Aryalib") (part "Resistor")))
    (comp (ref "R69") (value "470") (footprint "SMD 805") (libsource (lib "Aryalib") (part "Resistor")))
    (comp (ref "R70") (value "470") (footprint "SMD 805") (libsource (lib "Aryalib") (part "Resistor")))
    (comp (ref "R71") (value "470") (footprint "SMD 805") (libsource (lib "Aryalib") (part "Resistor")))
    (comp (ref "R72") (value "470") (footprint "SMD 805") (libsource (lib "Aryalib") (part "Resistor")))
    (comp (ref "R73") (value "470") (footprint "SMD 805") (libsource (lib "Aryalib") (part "Resistor")))
    (comp (ref "R74") (value "470") (footprint "SMD 805") (libsource (lib "Aryalib") (part "Resistor")))
    (comp (ref "R75") (value "470") (footprint "SMD 805") (libsource (lib "Aryalib") (part "Resistor")))
    (comp (ref "R76") (value "470") (footprint "SMD 805") (libsource (lib "Aryalib") (part "Resistor")))
    (comp (ref "R77") (value "470") (footprint "SMD 805") (libsource (lib "Aryalib") (part "Resistor")))
    (comp (ref "R78") (value "470") (footprint "SMD 805") (libsource (lib "Aryalib") (part "Resistor")))
    (comp (ref "R79") (value "470") (footprint "SMD 805") (libsource (lib "Aryalib") (part "Resistor")))
    (comp (ref "R80") (value "470") (footprint "SMD 805") (libsource (lib "Aryalib") (part "Resistor")))
    (comp (ref "U1")
      (value "LD1117 3.3")
      (footprint "MY_LD1117-3.3")
      (libsource (lib "AMINLIB") (part "LD1117 3.3"))
    )
  )
  (nets
    (net (code "1") (name "/3.3VRef") (class "Default")
      (node (ref "H2") (pin "1") (pinfunction "1_1") (pintype "passive"))
      (node (ref "POKERFACE1") (pin "3") (pinfunction "REF_3") (pintype "passive"))
      (node (ref "POKERFACE1") (pin "42") (pinfunction "REF_42") (pintype "passive"))
    )
    (net (code "2") (name "/NRST") (class "Default")
      (node (ref "H1") (pin "3") (pinfunction "3_3") (pintype "passive"))
      (node (ref "POKERFACE1") (pin "47") (pinfunction "NRST_47") (pintype "passive"))
      (node (ref "POKERFACE1") (pin "86") (pinfunction "NRST_86") (pintype "passive"))
    )
    (net (code "3") (name "/PA0") (class "Default")
      (node (ref "POKERFACE1") (pin "11") (pinfunction "A0_11") (pintype "passive"))
      (node (ref "R9") (pin "1") (pinfunction "1_1") (pintype "passive"))
    )
    (net (code "4") (name "/PA1") (class "Default")
      (node (ref "POKERFACE1") (pin "35") (pinfunction "A1_35") (pintype "passive"))
      (node (ref "R28") (pin "1") (pinfunction "1_1") (pintype "passive"))
    )
    (net (code "5") (name "/PA2") (class "Default")
      (node (ref "POKERFACE1") (pin "10") (pinfunction "A2_10") (pintype "passive"))
      (node (ref "R8") (pin "1") (pinfunction "1_1") (pintype "passive"))
    )
    (net (code "6") (name "/PA3") (class "Default")
      (node (ref "POKERFACE1") (pin "34") (pinfunction "A3_34") (pintype "passive"))
      (node (ref "R29") (pin "1") (pinfunction "1_1") (pintype "passive"))
    )
    (net (code "7") (name "/PA4") (class "Default")
      (node (ref "POKERFACE1") (pin "12") (pinfunction "A4_12") (pintype "passive"))
      (node (ref "R10") (pin "1") (pinfunction "1_1") (pintype "passive"))
    )
    (net (code "8") (name "/PA5") (class "Default")
      (node (ref "POKERFACE1") (pin "33") (pinfunction "A5_33") (pintype "passive"))
      (node (ref "R30") (pin "1") (pinfunction "1_1") (pintype "passive"))
    )
    (net (code "9") (name "/PA6") (class "Default")
      (node (ref "POKERFACE1") (pin "13") (pinfunction "A6_13") (pintype "passive"))
      (node (ref "R11") (pin "1") (pinfunction "1_1") (pintype "passive"))
    )
    (net (code "10") (name "/PA7") (class "Default")
      (node (ref "POKERFACE1") (pin "32") (pinfunction "A7_32") (pintype "passive"))
      (node (ref "R31") (pin "1") (pinfunction "1_1") (pintype "passive"))
    )
    (net (code "11") (name "/PA8") (class "Default")
      (node (ref "POKERFACE1") (pin "73") (pinfunction "A8_73") (pintype "passive"))
      (node (ref "R74") (pin "1") (pinfunction "1_1") (pintype "passive"))
    )
    (net (code "12") (name "/PA9") (class "Default")
      (node (ref "POKERFACE1") (pin "59") (pinfunction "A9_59") (pintype "passive"))
      (node (ref "R53") (pin "1") (pinfunction "1_1") (pintype "passive"))
    )
    (net (code "13") (name "/PA10") (class "Default")
      (node (ref "POKERFACE1") (pin "74") (pinfunction "A10_74") (pintype "passive"))
      (node (ref "R73") (pin "1") (pinfunction "1_1") (pintype "passive"))
    )
    (net (code "14") (name "/PA11") (class "Default")
      (node (ref "POKERFACE1") (pin "58") (pinfunction "A11_58") (pintype "passive"))
      (node (ref "R52") (pin "1") (pinfunction "1_1") (pintype "passive"))
    )
    (net (code "15") (name "/PA12") (class "Default")
      (node (ref "POKERFACE1") (pin "75") (pinfunction "A12_75") (pintype "passive"))
      (node (ref "R72") (pin "1") (pinfunction "1_1") (pintype "passive"))
    )
    (net (code "16") (name "/PA15") (class "Default")
      (node (ref "POKERFACE1") (pin "57") (pinfunction "A15_57") (pintype "passive"))
      (node (ref "R51") (pin "1") (pinfunction "1_1") (pintype "passive"))
    )
    (net (code "17") (name "/PB0") (class "Default")
      (node (ref "POKERFACE1") (pin "15") (pinfunction "B0_15") (pintype "passive"))
      (node (ref "R13") (pin "1") (pinfunction "1_1") (pintype "passive"))
    )
    (net (code "18") (name "/PB1") (class "Default")
      (node (ref "POKERFACE1") (pin "30") (pinfunction "B1_30") (pintype "passive"))
      (node (ref "R33") (pin "1") (pinfunction "1_1") (pintype "passive"))
    )
    (net (code "19") (name "/PB4") (class "Default")
      (node (ref "POKERFACE1") (pin "51") (pinfunction "B4_51") (pintype "passive"))
      (node (ref "R45") (pin "1") (pinfunction "1_1") (pintype "passive"))
    )
    (net (code "20") (name "/PB5") (class "Default")
      (node (ref "POKERFACE1") (pin "82") (pinfunction "B5_82") (pintype "passive"))
      (node (ref "R65") (pin "1") (pinfunction "1_1") (pintype "passive"))
    )
    (net (code "21") (name "/PB6") (class "Default")
      (node (ref "POKERFACE1") (pin "50") (pinfunction "B6_50") (pintype "passive"))
      (node (ref "R44") (pin "1") (pinfunction "1_1") (pintype "passive"))
    )
    (net (code "22") (name "/PB7") (class "Default")
      (node (ref "POKERFACE1") (pin "83") (pinfunction "B7_83") (pintype "passive"))
      (node (ref "R64") (pin "1") (pinfunction "1_1") (pintype "passive"))
    )
    (net (code "23") (name "/PB8") (class "Default")
      (node (ref "POKERFACE1") (pin "49") (pinfunction "B8_49") (pintype "passive"))
      (node (ref "R43") (pin "1") (pinfunction "1_1") (pintype "passive"))
    )
    (net (code "24") (name "/PB9") (class "Default")
      (node (ref "POKERFACE1") (pin "84") (pinfunction "B9_84") (pintype "passive"))
      (node (ref "R63") (pin "1") (pinfunction "1_1") (pintype "passive"))
    )
    (net (code "25") (name "/PB10") (class "Default")
      (node (ref "POKERFACE1") (pin "25") (pinfunction "B10_25") (pintype "passive"))
      (node (ref "R38") (pin "1") (pinfunction "1_1") (pintype "passive"))
    )
    (net (code "26") (name "/PB11") (class "Default")
      (node (ref "POKERFACE1") (pin "21") (pinfunction "B11_21") (pintype "passive"))
      (node (ref "R19") (pin "1") (pinfunction "1_1") (pintype "passive"))
    )
    (net (code "27") (name "/PB12") (class "Default")
      (node (ref "POKERFACE1") (pin "24") (pinfunction "B12_24") (pintype "passive"))
      (node (ref "R39") (pin "1") (pinfunction "1_1") (pintype "passive"))
    )
    (net (code "28") (name "/PB13") (class "Default")
      (node (ref "POKERFACE1") (pin "22") (pinfunction "B13_22") (pintype "passive"))
      (node (ref "R20") (pin "1") (pinfunction "1_1") (pintype "passive"))
    )
    (net (code "29") (name "/PB14") (class "Default")
      (node (ref "POKERFACE1") (pin "23") (pinfunction "B14_23") (pintype "passive"))
      (node (ref "R40") (pin "1") (pinfunction "1_1") (pintype "passive"))
    )
    (net (code "30") (name "/PB15") (class "Default")
      (node (ref "POKERFACE1") (pin "66") (pinfunction "B15_66") (pintype "passive"))
      (node (ref "R60") (pin "1") (pinfunction "1_1") (pintype "passive"))
    )
    (net (code "31") (name "/PC0") (class "Default")
      (node (ref "POKERFACE1") (pin "8") (pinfunction "C0_8") (pintype "passive"))
      (node (ref "R6") (pin "1") (pinfunction "1_1") (pintype "passive"))
    )
    (net (code "32") (name "/PC1") (class "Default")
      (node (ref "POKERFACE1") (pin "37") (pinfunction "C1_37") (pintype "passive"))
      (node (ref "R26") (pin "1") (pinfunction "1_1") (pintype "passive"))
    )
    (net (code "33") (name "/PC2") (class "Default")
      (node (ref "POKERFACE1") (pin "9") (pinfunction "C2_9") (pintype "passive"))
      (node (ref "R7") (pin "1") (pinfunction "1_1") (pintype "passive"))
    )
    (net (code "34") (name "/PC3") (class "Default")
      (node (ref "POKERFACE1") (pin "36") (pinfunction "C3_36") (pintype "passive"))
      (node (ref "R27") (pin "1") (pinfunction "1_1") (pintype "passive"))
    )
    (net (code "35") (name "/PC4") (class "Default")
      (node (ref "POKERFACE1") (pin "14") (pinfunction "C4_14") (pintype "passive"))
      (node (ref "R12") (pin "1") (pinfunction "1_1") (pintype "passive"))
    )
    (net (code "36") (name "/PC5") (class "Default")
      (node (ref "POKERFACE1") (pin "31") (pinfunction "C5_31") (pintype "passive"))
      (node (ref "R32") (pin "1") (pinfunction "1_1") (pintype "passive"))
    )
    (net (code "37") (name "/PC6") (class "Default")
      (node (ref "POKERFACE1") (pin "71") (pinfunction "C6_71") (pintype "passive"))
      (node (ref "R76") (pin "1") (pinfunction "1_1") (pintype "passive"))
    )
    (net (code "38") (name "/PC7") (class "Default")
      (node (ref "POKERFACE1") (pin "61") (pinfunction "C7_61") (pintype "passive"))
      (node (ref "R55") (pin "1") (pinfunction "1_1") (pintype "passive"))
    )
    (net (code "39") (name "/PC8") (class "Default")
      (node (ref "POKERFACE1") (pin "72") (pinfunction "C8_72") (pintype "passive"))
      (node (ref "R75") (pin "1") (pinfunction "1_1") (pintype "passive"))
    )
    (net (code "40") (name "/PC9") (class "Default")
      (node (ref "POKERFACE1") (pin "60") (pinfunction "C9_60") (pintype "passive"))
      (node (ref "R54") (pin "1") (pinfunction "1_1") (pintype "passive"))
    )
    (net (code "41") (name "/PC10") (class "Default")
      (node (ref "POKERFACE1") (pin "76") (pinfunction "C10_76") (pintype "passive"))
      (node (ref "R71") (pin "1") (pinfunction "1_1") (pintype "passive"))
    )
    (net (code "42") (name "/PC11") (class "Default")
      (node (ref "POKERFACE1") (pin "56") (pinfunction "C11_56") (pintype "passive"))
      (node (ref "R50") (pin "1") (pinfunction "1_1") (pintype "passive"))
    )
    (net (code "43") (name "/PC12") (class "Default")
      (node (ref "POKERFACE1") (pin "77") (pinfunction "C12_77") (pintype "passive"))
      (node (ref "R70") (pin "1") (pinfunction "1_1") (pintype "passive"))
    )
    (net (code "44") (name "/PC13") (class "Default")
      (node (ref "POKERFACE1") (pin "39") (pinfunction "C13_39") (pintype "passive"))
      (node (ref "R24") (pin "1") (pinfunction "1_1") (pintype "passive"))
    )
    (net (code "45") (name "/PC14") (class "Default")
      (node (ref "POKERFACE1") (pin "7") (pinfunction "C14_7") (pintype "passive"))
      (node (ref "R5") (pin "1") (pinfunction "1_1") (pintype "passive"))
    )
    (net (code "46") (name "/PC15") (class "Default")
      (node (ref "POKERFACE1") (pin "38") (pinfunction "C15_38") (pintype "passive"))
      (node (ref "R25") (pin "1") (pinfunction "1_1") (pintype "passive"))
    )
    (net (code "47") (name "/PD0") (class "Default")
      (node (ref "POKERFACE1") (pin "55") (pinfunction "D0_55") (pintype "passive"))
      (node (ref "R49") (pin "1") (pinfunction "1_1") (pintype "passive"))
    )
    (net (code "48") (name "/PD1") (class "Default")
      (node (ref "POKERFACE1") (pin "78") (pinfunction "D1_78") (pintype "passive"))
      (node (ref "R69") (pin "1") (pinfunction "1_1") (pintype "passive"))
    )
    (net (code "49") (name "/PD2") (class "Default")
      (node (ref "POKERFACE1") (pin "54") (pinfunction "D2_54") (pintype "passive"))
      (node (ref "R48") (pin "1") (pinfunction "1_1") (pintype "passive"))
    )
    (net (code "50") (name "/PD3") (class "Default")
      (node (ref "POKERFACE1") (pin "79") (pinfunction "D3_79") (pintype "passive"))
      (node (ref "R68") (pin "1") (pinfunction "1_1") (pintype "passive"))
    )
    (net (code "51") (name "/PD4") (class "Default")
      (node (ref "POKERFACE1") (pin "53") (pinfunction "D4_53") (pintype "passive"))
      (node (ref "R47") (pin "1") (pinfunction "1_1") (pintype "passive"))
    )
    (net (code "52") (name "/PD5") (class "Default")
      (node (ref "POKERFACE1") (pin "80") (pinfunction "D5_80") (pintype "passive"))
      (node (ref "R67") (pin "1") (pinfunction "1_1") (pintype "passive"))
    )
    (net (code "53") (name "/PD6") (class "Default")
      (node (ref "POKERFACE1") (pin "52") (pinfunction "D6_52") (pintype "passive"))
      (node (ref "R46") (pin "1") (pinfunction "1_1") (pintype "passive"))
    )
    (net (code "54") (name "/PD7") (class "Default")
      (node (ref "POKERFACE1") (pin "81") (pinfunction "D7_81") (pintype "passive"))
      (node (ref "R66") (pin "1") (pinfunction "1_1") (pintype "passive"))
    )
    (net (code "55") (name "/PD8") (class "Default")
      (node (ref "POKERFACE1") (pin "67") (pinfunction "D8_67") (pintype "passive"))
      (node (ref "R80") (pin "1") (pinfunction "1_1") (pintype "passive"))
    )
    (net (code "56") (name "/PD9") (class "Default")
      (node (ref "POKERFACE1") (pin "65") (pinfunction "D9_65") (pintype "passive"))
      (node (ref "R59") (pin "1") (pinfunction "1_1") (pintype "passive"))
    )
    (net (code "57") (name "/PD10") (class "Default")
      (node (ref "POKERFACE1") (pin "68") (pinfunction "D10_68") (pintype "passive"))
      (node (ref "R79") (pin "1") (pinfunction "1_1") (pintype "passive"))
    )
    (net (code "58") (name "/PD11") (class "Default")
      (node (ref "POKERFACE1") (pin "64") (pinfunction "D11_64") (pintype "passive"))
      (node (ref "R58") (pin "1") (pinfunction "1_1") (pintype "passive"))
    )
    (net (code "59") (name "/PD12") (class "Default")
      (node (ref "POKERFACE1") (pin "69") (pinfunction "D12L1_69") (pintype "passive"))
      (node (ref "R78") (pin "1") (pinfunction "1_1") (pintype "passive"))
    )
    (net (code "60") (name "/PD13") (class "Default")
      (node (ref "POKERFACE1") (pin "63") (pinfunction "D13L2_63") (pintype "passive"))
      (node (ref "R57") (pin "1") (pinfunction "1_1") (pintype "passive"))
    )
    (net (code "61") (name "/PD14") (class "Default")
      (node (ref "POKERFACE1") (pin "70") (pinfunction "D14L3_70") (pintype "passive"))
      (node (ref "R77") (pin "1") (pinfunction "1_1") (pintype "passive"))
    )
    (net (code "62") (name "/PD15") (class "Default")
      (node (ref "POKERFACE1") (pin "62") (pinfunction "D15L4_62") (pintype "passive"))
      (node (ref "R56") (pin "1") (pinfunction "1_1") (pintype "passive"))
    )
    (net (code "63") (name "/PE0") (class "Default")
      (node (ref "POKERFACE1") (pin "48") (pinfunction "E0_48") (pintype "passive"))
      (node (ref "R42") (pin "1") (pinfunction "1_1") (pintype "passive"))
    )
    (net (code "64") (name "/PE1") (class "Default")
      (node (ref "POKERFACE1") (pin "85") (pinfunction "E1_85") (pintype "passive"))
      (node (ref "R62") (pin "1") (pinfunction "1_1") (pintype "passive"))
    )
    (net (code "65") (name "/PE2") (class "Default")
      (node (ref "POKERFACE1") (pin "4") (pinfunction "E2_4") (pintype "passive"))
      (node (ref "R2") (pin "1") (pinfunction "1_1") (pintype "passive"))
    )
    (net (code "66") (name "/PE3") (class "Default")
      (node (ref "POKERFACE1") (pin "41") (pinfunction "E3_41") (pintype "passive"))
      (node (ref "R22") (pin "1") (pinfunction "1_1") (pintype "passive"))
    )
    (net (code "67") (name "/PE4") (class "Default")
      (node (ref "POKERFACE1") (pin "5") (pinfunction "E4_5") (pintype "passive"))
      (node (ref "R3") (pin "1") (pinfunction "1_1") (pintype "passive"))
    )
    (net (code "68") (name "/PE5") (class "Default")
      (node (ref "POKERFACE1") (pin "40") (pinfunction "E5_40") (pintype "passive"))
      (node (ref "R23") (pin "1") (pinfunction "1_1") (pintype "passive"))
    )
    (net (code "69") (name "/PE6") (class "Default")
      (node (ref "POKERFACE1") (pin "6") (pinfunction "E6_6") (pintype "passive"))
      (node (ref "R4") (pin "1") (pinfunction "1_1") (pintype "passive"))
    )
    (net (code "70") (name "/PE7") (class "Default")
      (node (ref "POKERFACE1") (pin "16") (pinfunction "E7_16") (pintype "passive"))
      (node (ref "R14") (pin "1") (pinfunction "1_1") (pintype "passive"))
    )
    (net (code "71") (name "/PE8") (class "Default")
      (node (ref "POKERFACE1") (pin "29") (pinfunction "E8_29") (pintype "passive"))
      (node (ref "R34") (pin "1") (pinfunction "1_1") (pintype "passive"))
    )
    (net (code "72") (name "/PE9") (class "Default")
      (node (ref "POKERFACE1") (pin "17") (pinfunction "E9_17") (pintype "passive"))
      (node (ref "R15") (pin "1") (pinfunction "1_1") (pintype "passive"))
    )
    (net (code "73") (name "/PE10") (class "Default")
      (node (ref "POKERFACE1") (pin "28") (pinfunction "E10_28") (pintype "passive"))
      (node (ref "R35") (pin "1") (pinfunction "1_1") (pintype "passive"))
    )
    (net (code "74") (name "/PE11") (class "Default")
      (node (ref "POKERFACE1") (pin "18") (pinfunction "E11_18") (pintype "passive"))
      (node (ref "R16") (pin "1") (pinfunction "1_1") (pintype "passive"))
    )
    (net (code "75") (name "/PE12") (class "Default")
      (node (ref "POKERFACE1") (pin "27") (pinfunction "E12_27") (pintype "passive"))
      (node (ref "R36") (pin "1") (pinfunction "1_1") (pintype "passive"))
    )
    (net (code "76") (name "/PE13") (class "Default")
      (node (ref "POKERFACE1") (pin "19") (pinfunction "E13_19") (pintype "passive"))
      (node (ref "R17") (pin "1") (pinfunction "1_1") (pintype "passive"))
    )
    (net (code "77") (name "/PE14") (class "Default")
      (node (ref "POKERFACE1") (pin "26") (pinfunction "E14_26") (pintype "passive"))
      (node (ref "R37") (pin "1") (pinfunction "1_1") (pintype "passive"))
    )
    (net (code "78") (name "/PE15") (class "Default")
      (node (ref "POKERFACE1") (pin "20") (pinfunction "E15_20") (pintype "passive"))
      (node (ref "R18") (pin "1") (pinfunction "1_1") (pintype "passive"))
    )
    (net (code "79") (name "3.3V") (class "Default")
      (node (ref "C2") (pin "+") (pinfunction "+_+") (pintype "passive"))
      (node (ref "H1") (pin "2") (pinfunction "2_2") (pintype "passive"))
      (node (ref "J2") (pin "1") (pinfunction "1_1") (pintype "passive"))
      (node (ref "POKERFACE1") (pin "46") (pinfunction "3.3V_46") (pintype "passive"))
      (node (ref "POKERFACE1") (pin "87") (pinfunction "3.3V_87") (pintype "passive"))
      (node (ref "R41") (pin "1") (pinfunction "1_1") (pintype "passive"))
      (node (ref "U1") (pin "2") (pinfunction "OUT_2") (pintype "power_in"))
      (node (ref "U1") (pin "4") (pinfunction "OUT_4") (pintype "power_in"))
    )
    (net (code "80") (name "5V") (class "Default")
      (node (ref "C1") (pin "+") (pinfunction "+_+") (pintype "passive"))
      (node (ref "H2") (pin "2") (pinfunction "2_2") (pintype "passive"))
      (node (ref "J1") (pin "1") (pinfunction "1_1") (pintype "passive"))
      (node (ref "POKERFACE1") (pin "2") (pinfunction "5V_2") (pintype "passive"))
      (node (ref "POKERFACE1") (pin "43") (pinfunction "5V_43") (pintype "passive"))
      (node (ref "R1") (pin "1") (pinfunction "1_1") (pintype "passive"))
      (node (ref "U1") (pin "3") (pinfunction "IN_3") (pintype "power_in"))
    )
    (net (code "81") (name "GND") (class "Default")
      (node (ref "C1") (pin "-") (pinfunction "-_-") (pintype "passive"))
      (node (ref "C2") (pin "-") (pinfunction "-_-") (pintype "passive"))
      (node (ref "H1") (pin "1") (pinfunction "1_1") (pintype "passive"))
      (node (ref "H2") (pin "3") (pinfunction "3_3") (pintype "passive"))
      (node (ref "J1") (pin "2") (pinfunction "2_2") (pintype "passive"))
      (node (ref "J2") (pin "2") (pinfunction "2_2") (pintype "passive"))
      (node (ref "LED1") (pin "2") (pinfunction "C_2") (pintype "passive"))
      (node (ref "LED10") (pin "2") (pinfunction "C_2") (pintype "passive"))
      (node (ref "LED11") (pin "2") (pinfunction "C_2") (pintype "passive"))
      (node (ref "LED12") (pin "2") (pinfunction "C_2") (pintype "passive"))
      (node (ref "LED13") (pin "2") (pinfunction "C_2") (pintype "passive"))
      (node (ref "LED14") (pin "2") (pinfunction "C_2") (pintype "passive"))
      (node (ref "LED15") (pin "2") (pinfunction "C_2") (pintype "passive"))
      (node (ref "LED16") (pin "2") (pinfunction "C_2") (pintype "passive"))
      (node (ref "LED17") (pin "2") (pinfunction "C_2") (pintype "passive"))
      (node (ref "LED18") (pin "2") (pinfunction "C_2") (pintype "passive"))
      (node (ref "LED19") (pin "2") (pinfunction "C_2") (pintype "passive"))
      (node (ref "LED2") (pin "2") (pinfunction "C_2") (pintype "passive"))
      (node (ref "LED20") (pin "2") (pinfunction "C_2") (pintype "passive"))
      (node (ref "LED22") (pin "2") (pinfunction "C_2") (pintype "passive"))
      (node (ref "LED23") (pin "2") (pinfunction "C_2") (pintype "passive"))
      (node (ref "LED24") (pin "2") (pinfunction "C_2") (pintype "passive"))
      (node (ref "LED25") (pin "2") (pinfunction "C_2") (pintype "passive"))
      (node (ref "LED26") (pin "2") (pinfunction "C_2") (pintype "passive"))
      (node (ref "LED27") (pin "2") (pinfunction "C_2") (pintype "passive"))
      (node (ref "LED28") (pin "2") (pinfunction "C_2") (pintype "passive"))
      (node (ref "LED29") (pin "2") (pinfunction "C_2") (pintype "passive"))
      (node (ref "LED3") (pin "2") (pinfunction "C_2") (pintype "passive"))
      (node (ref "LED30") (pin "2") (pinfunction "C_2") (pintype "passive"))
      (node (ref "LED31") (pin "2") (pinfunction "C_2") (pintype "passive"))
      (node (ref "LED32") (pin "2") (pinfunction "C_2") (pintype "passive"))
      (node (ref "LED33") (pin "2") (pinfunction "C_2") (pintype "passive"))
      (node (ref "LED34") (pin "2") (pinfunction "C_2") (pintype "passive"))
      (node (ref "LED35") (pin "2") (pinfunction "C_2") (pintype "passive"))
      (node (ref "LED36") (pin "2") (pinfunction "C_2") (pintype "passive"))
      (node (ref "LED37") (pin "2") (pinfunction "C_2") (pintype "passive"))
      (node (ref "LED38") (pin "2") (pinfunction "C_2") (pintype "passive"))
      (node (ref "LED39") (pin "2") (pinfunction "C_2") (pintype "passive"))
      (node (ref "LED4") (pin "2") (pinfunction "C_2") (pintype "passive"))
      (node (ref "LED40") (pin "2") (pinfunction "C_2") (pintype "passive"))
      (node (ref "LED41") (pin "2") (pinfunction "C_2") (pintype "passive"))
      (node (ref "LED42") (pin "2") (pinfunction "C_2") (pintype "passive"))
      (node (ref "LED43") (pin "2") (pinfunction "C_2") (pintype "passive"))
      (node (ref "LED44") (pin "2") (pinfunction "C_2") (pintype "passive"))
      (node (ref "LED45") (pin "2") (pinfunction "C_2") (pintype "passive"))
      (node (ref "LED46") (pin "2") (pinfunction "C_2") (pintype "passive"))
      (node (ref "LED47") (pin "2") (pinfunction "C_2") (pintype "passive"))
      (node (ref "LED48") (pin "2") (pinfunction "C_2") (pintype "passive"))
      (node (ref "LED49") (pin "2") (pinfunction "C_2") (pintype "passive"))
      (node (ref "LED5") (pin "2") (pinfunction "C_2") (pintype "passive"))
      (node (ref "LED50") (pin "2") (pinfunction "C_2") (pintype "passive"))
      (node (ref "LED51") (pin "2") (pinfunction "C_2") (pintype "passive"))
      (node (ref "LED52") (pin "2") (pinfunction "C_2") (pintype "passive"))
      (node (ref "LED53") (pin "2") (pinfunction "C_2") (pintype "passive"))
      (node (ref "LED54") (pin "2") (pinfunction "C_2") (pintype "passive"))
      (node (ref "LED55") (pin "2") (pinfunction "C_2") (pintype "passive"))
      (node (ref "LED56") (pin "2") (pinfunction "C_2") (pintype "passive"))
      (node (ref "LED57") (pin "2") (pinfunction "C_2") (pintype "passive"))
      (node (ref "LED58") (pin "2") (pinfunction "C_2") (pintype "passive"))
      (node (ref "LED59") (pin "2") (pinfunction "C_2") (pintype "passive"))
      (node (ref "LED6") (pin "2") (pinfunction "C_2") (pintype "passive"))
      (node (ref "LED60") (pin "2") (pinfunction "C_2") (pintype "passive"))
      (node (ref "LED62") (pin "2") (pinfunction "C_2") (pintype "passive"))
      (node (ref "LED63") (pin "2") (pinfunction "C_2") (pintype "passive"))
      (node (ref "LED64") (pin "2") (pinfunction "C_2") (pintype "passive"))
      (node (ref "LED65") (pin "2") (pinfunction "C_2") (pintype "passive"))
      (node (ref "LED66") (pin "2") (pinfunction "C_2") (pintype "passive"))
      (node (ref "LED67") (pin "2") (pinfunction "C_2") (pintype "passive"))
      (node (ref "LED68") (pin "2") (pinfunction "C_2") (pintype "passive"))
      (node (ref "LED69") (pin "2") (pinfunction "C_2") (pintype "passive"))
      (node (ref "LED7") (pin "2") (pinfunction "C_2") (pintype "passive"))
      (node (ref "LED70") (pin "2") (pinfunction "C_2") (pintype "passive"))
      (node (ref "LED71") (pin "2") (pinfunction "C_2") (pintype "passive"))
      (node (ref "LED72") (pin "2") (pinfunction "C_2") (pintype "passive"))
      (node (ref "LED73") (pin "2") (pinfunction "C_2") (pintype "passive"))
      (node (ref "LED74") (pin "2") (pinfunction "C_2") (pintype "passive"))
      (node (ref "LED75") (pin "2") (pinfunction "C_2") (pintype "passive"))
      (node (ref "LED76") (pin "2") (pinfunction "C_2") (pintype "passive"))
      (node (ref "LED77") (pin "2") (pinfunction "C_2") (pintype "passive"))
      (node (ref "LED78") (pin "2") (pinfunction "C_2") (pintype "passive"))
      (node (ref "LED79") (pin "2") (pinfunction "C_2") (pintype "passive"))
      (node (ref "LED8") (pin "2") (pinfunction "C_2") (pintype "passive"))
      (node (ref "LED80") (pin "2") (pinfunction "C_2") (pintype "passive"))
      (node (ref "LED9") (pin "2") (pinfunction "C_2") (pintype "passive"))
      (node (ref "POKERFACE1") (pin "1") (pinfunction "GND_1") (pintype "passive"))
      (node (ref "POKERFACE1") (pin "44") (pinfunction "GND_44") (pintype "passive"))
      (node (ref "POKERFACE1") (pin "45") (pinfunction "GND_45") (pintype "passive"))
      (node (ref "POKERFACE1") (pin "88") (pinfunction "GND_88") (pintype "passive"))
      (node (ref "U1") (pin "1") (pinfunction "GND_1") (pintype "power_in"))
    )
    (net (code "82") (name "Net-(LED1-A)") (class "Default")
      (node (ref "LED1") (pin "1") (pinfunction "A_1") (pintype "passive"))
      (node (ref "R1") (pin "2") (pinfunction "2_2") (pintype "passive"))
    )
    (net (code "83") (name "Net-(LED2-A)") (class "Default")
      (node (ref "LED2") (pin "1") (pinfunction "A_1") (pintype "passive"))
      (node (ref "R2") (pin "2") (pinfunction "2_2") (pintype "passive"))
    )
    (net (code "84") (name "Net-(LED3-A)") (class "Default")
      (node (ref "LED3") (pin "1") (pinfunction "A_1") (pintype "passive"))
      (node (ref "R3") (pin "2") (pinfunction "2_2") (pintype "passive"))
    )
    (net (code "85") (name "Net-(LED4-A)") (class "Default")
      (node (ref "LED4") (pin "1") (pinfunction "A_1") (pintype "passive"))
      (node (ref "R4") (pin "2") (pinfunction "2_2") (pintype "passive"))
    )
    (net (code "86") (name "Net-(LED5-A)") (class "Default")
      (node (ref "LED5") (pin "1") (pinfunction "A_1") (pintype "passive"))
      (node (ref "R5") (pin "2") (pinfunction "2_2") (pintype "passive"))
    )
    (net (code "87") (name "Net-(LED6-A)") (class "Default")
      (node (ref "LED6") (pin "1") (pinfunction "A_1") (pintype "passive"))
      (node (ref "R6") (pin "2") (pinfunction "2_2") (pintype "passive"))
    )
    (net (code "88") (name "Net-(LED7-A)") (class "Default")
      (node (ref "LED7") (pin "1") (pinfunction "A_1") (pintype "passive"))
      (node (ref "R7") (pin "2") (pinfunction "2_2") (pintype "passive"))
    )
    (net (code "89") (name "Net-(LED8-A)") (class "Default")
      (node (ref "LED8") (pin "1") (pinfunction "A_1") (pintype "passive"))
      (node (ref "R8") (pin "2") (pinfunction "2_2") (pintype "passive"))
    )
    (net (code "90") (name "Net-(LED9-A)") (class "Default")
      (node (ref "LED9") (pin "1") (pinfunction "A_1") (pintype "passive"))
      (node (ref "R9") (pin "2") (pinfunction "2_2") (pintype "passive"))
    )
    (net (code "91") (name "Net-(LED10-A)") (class "Default")
      (node (ref "LED10") (pin "1") (pinfunction "A_1") (pintype "passive"))
      (node (ref "R10") (pin "2") (pinfunction "2_2") (pintype "passive"))
    )
    (net (code "92") (name "Net-(LED11-A)") (class "Default")
      (node (ref "LED11") (pin "1") (pinfunction "A_1") (pintype "passive"))
      (node (ref "R11") (pin "2") (pinfunction "2_2") (pintype "passive"))
    )
    (net (code "93") (name "Net-(LED12-A)") (class "Default")
      (node (ref "LED12") (pin "1") (pinfunction "A_1") (pintype "passive"))
      (node (ref "R12") (pin "2") (pinfunction "2_2") (pintype "passive"))
    )
    (net (code "94") (name "Net-(LED13-A)") (class "Default")
      (node (ref "LED13") (pin "1") (pinfunction "A_1") (pintype "passive"))
      (node (ref "R13") (pin "2") (pinfunction "2_2") (pintype "passive"))
    )
    (net (code "95") (name "Net-(LED14-A)") (class "Default")
      (node (ref "LED14") (pin "1") (pinfunction "A_1") (pintype "passive"))
      (node (ref "R14") (pin "2") (pinfunction "2_2") (pintype "passive"))
    )
    (net (code "96") (name "Net-(LED15-A)") (class "Default")
      (node (ref "LED15") (pin "1") (pinfunction "A_1") (pintype "passive"))
      (node (ref "R15") (pin "2") (pinfunction "2_2") (pintype "passive"))
    )
    (net (code "97") (name "Net-(LED16-A)") (class "Default")
      (node (ref "LED16") (pin "1") (pinfunction "A_1") (pintype "passive"))
      (node (ref "R16") (pin "2") (pinfunction "2_2") (pintype "passive"))
    )
    (net (code "98") (name "Net-(LED17-A)") (class "Default")
      (node (ref "LED17") (pin "1") (pinfunction "A_1") (pintype "passive"))
      (node (ref "R17") (pin "2") (pinfunction "2_2") (pintype "passive"))
    )
    (net (code "99") (name "Net-(LED18-A)") (class "Default")
      (node (ref "LED18") (pin "1") (pinfunction "A_1") (pintype "passive"))
      (node (ref "R18") (pin "2") (pinfunction "2_2") (pintype "passive"))
    )
    (net (code "100") (name "Net-(LED19-A)") (class "Default")
      (node (ref "LED19") (pin "1") (pinfunction "A_1") (pintype "passive"))
      (node (ref "R19") (pin "2") (pinfunction "2_2") (pintype "passive"))
    )
    (net (code "101") (name "Net-(LED20-A)") (class "Default")
      (node (ref "LED20") (pin "1") (pinfunction "A_1") (pintype "passive"))
      (node (ref "R20") (pin "2") (pinfunction "2_2") (pintype "passive"))
    )
    (net (code "102") (name "Net-(LED22-A)") (class "Default")
      (node (ref "LED22") (pin "1") (pinfunction "A_1") (pintype "passive"))
      (node (ref "R22") (pin "2") (pinfunction "2_2") (pintype "passive"))
    )
    (net (code "103") (name "Net-(LED23-A)") (class "Default")
      (node (ref "LED23") (pin "1") (pinfunction "A_1") (pintype "passive"))
      (node (ref "R23") (pin "2") (pinfunction "2_2") (pintype "passive"))
    )
    (net (code "104") (name "Net-(LED24-A)") (class "Default")
      (node (ref "LED24") (pin "1") (pinfunction "A_1") (pintype "passive"))
      (node (ref "R24") (pin "2") (pinfunction "2_2") (pintype "passive"))
    )
    (net (code "105") (name "Net-(LED25-A)") (class "Default")
      (node (ref "LED25") (pin "1") (pinfunction "A_1") (pintype "passive"))
      (node (ref "R25") (pin "2") (pinfunction "2_2") (pintype "passive"))
    )
    (net (code "106") (name "Net-(LED26-A)") (class "Default")
      (node (ref "LED26") (pin "1") (pinfunction "A_1") (pintype "passive"))
      (node (ref "R26") (pin "2") (pinfunction "2_2") (pintype "passive"))
    )
    (net (code "107") (name "Net-(LED27-A)") (class "Default")
      (node (ref "LED27") (pin "1") (pinfunction "A_1") (pintype "passive"))
      (node (ref "R27") (pin "2") (pinfunction "2_2") (pintype "passive"))
    )
    (net (code "108") (name "Net-(LED28-A)") (class "Default")
      (node (ref "LED28") (pin "1") (pinfunction "A_1") (pintype "passive"))
      (node (ref "R28") (pin "2") (pinfunction "2_2") (pintype "passive"))
    )
    (net (code "109") (name "Net-(LED29-A)") (class "Default")
      (node (ref "LED29") (pin "1") (pinfunction "A_1") (pintype "passive"))
      (node (ref "R29") (pin "2") (pinfunction "2_2") (pintype "passive"))
    )
    (net (code "110") (name "Net-(LED30-A)") (class "Default")
      (node (ref "LED30") (pin "1") (pinfunction "A_1") (pintype "passive"))
      (node (ref "R30") (pin "2") (pinfunction "2_2") (pintype "passive"))
    )
    (net (code "111") (name "Net-(LED31-A)") (class "Default")
      (node (ref "LED31") (pin "1") (pinfunction "A_1") (pintype "passive"))
      (node (ref "R31") (pin "2") (pinfunction "2_2") (pintype "passive"))
    )
    (net (code "112") (name "Net-(LED32-A)") (class "Default")
      (node (ref "LED32") (pin "1") (pinfunction "A_1") (pintype "passive"))
      (node (ref "R32") (pin "2") (pinfunction "2_2") (pintype "passive"))
    )
    (net (code "113") (name "Net-(LED33-A)") (class "Default")
      (node (ref "LED33") (pin "1") (pinfunction "A_1") (pintype "passive"))
      (node (ref "R33") (pin "2") (pinfunction "2_2") (pintype "passive"))
    )
    (net (code "114") (name "Net-(LED34-A)") (class "Default")
      (node (ref "LED34") (pin "1") (pinfunction "A_1") (pintype "passive"))
      (node (ref "R34") (pin "2") (pinfunction "2_2") (pintype "passive"))
    )
    (net (code "115") (name "Net-(LED35-A)") (class "Default")
      (node (ref "LED35") (pin "1") (pinfunction "A_1") (pintype "passive"))
      (node (ref "R35") (pin "2") (pinfunction "2_2") (pintype "passive"))
    )
    (net (code "116") (name "Net-(LED36-A)") (class "Default")
      (node (ref "LED36") (pin "1") (pinfunction "A_1") (pintype "passive"))
      (node (ref "R36") (pin "2") (pinfunction "2_2") (pintype "passive"))
    )
    (net (code "117") (name "Net-(LED37-A)") (class "Default")
      (node (ref "LED37") (pin "1") (pinfunction "A_1") (pintype "passive"))
      (node (ref "R37") (pin "2") (pinfunction "2_2") (pintype "passive"))
    )
    (net (code "118") (name "Net-(LED38-A)") (class "Default")
      (node (ref "LED38") (pin "1") (pinfunction "A_1") (pintype "passive"))
      (node (ref "R38") (pin "2") (pinfunction "2_2") (pintype "passive"))
    )
    (net (code "119") (name "Net-(LED39-A)") (class "Default")
      (node (ref "LED39") (pin "1") (pinfunction "A_1") (pintype "passive"))
      (node (ref "R39") (pin "2") (pinfunction "2_2") (pintype "passive"))
    )
    (net (code "120") (name "Net-(LED40-A)") (class "Default")
      (node (ref "LED40") (pin "1") (pinfunction "A_1") (pintype "passive"))
      (node (ref "R40") (pin "2") (pinfunction "2_2") (pintype "passive"))
    )
    (net (code "121") (name "Net-(LED41-A)") (class "Default")
      (node (ref "LED41") (pin "1") (pinfunction "A_1") (pintype "passive"))
      (node (ref "R41") (pin "2") (pinfunction "2_2") (pintype "passive"))
    )
    (net (code "122") (name "Net-(LED42-A)") (class "Default")
      (node (ref "LED42") (pin "1") (pinfunction "A_1") (pintype "passive"))
      (node (ref "R42") (pin "2") (pinfunction "2_2") (pintype "passive"))
    )
    (net (code "123") (name "Net-(LED43-A)") (class "Default")
      (node (ref "LED43") (pin "1") (pinfunction "A_1") (pintype "passive"))
      (node (ref "R43") (pin "2") (pinfunction "2_2") (pintype "passive"))
    )
    (net (code "124") (name "Net-(LED44-A)") (class "Default")
      (node (ref "LED44") (pin "1") (pinfunction "A_1") (pintype "passive"))
      (node (ref "R44") (pin "2") (pinfunction "2_2") (pintype "passive"))
    )
    (net (code "125") (name "Net-(LED45-A)") (class "Default")
      (node (ref "LED45") (pin "1") (pinfunction "A_1") (pintype "passive"))
      (node (ref "R45") (pin "2") (pinfunction "2_2") (pintype "passive"))
    )
    (net (code "126") (name "Net-(LED46-A)") (class "Default")
      (node (ref "LED46") (pin "1") (pinfunction "A_1") (pintype "passive"))
      (node (ref "R46") (pin "2") (pinfunction "2_2") (pintype "passive"))
    )
    (net (code "127") (name "Net-(LED47-A)") (class "Default")
      (node (ref "LED47") (pin "1") (pinfunction "A_1") (pintype "passive"))
      (node (ref "R47") (pin "2") (pinfunction "2_2") (pintype "passive"))
    )
    (net (code "128") (name "Net-(LED48-A)") (class "Default")
      (node (ref "LED48") (pin "1") (pinfunction "A_1") (pintype "passive"))
      (node (ref "R48") (pin "2") (pinfunction "2_2") (pintype "passive"))
    )
    (net (code "129") (name "Net-(LED49-A)") (class "Default")
      (node (ref "LED49") (pin "1") (pinfunction "A_1") (pintype "passive"))
      (node (ref "R49") (pin "2") (pinfunction "2_2") (pintype "passive"))
    )
    (net (code "130") (name "Net-(LED50-A)") (class "Default")
      (node (ref "LED50") (pin "1") (pinfunction "A_1") (pintype "passive"))
      (node (ref "R50") (pin "2") (pinfunction "2_2") (pintype "passive"))
    )
    (net (code "131") (name "Net-(LED51-A)") (class "Default")
      (node (ref "LED51") (pin "1") (pinfunction "A_1") (pintype "passive"))
      (node (ref "R51") (pin "2") (pinfunction "2_2") (pintype "passive"))
    )
    (net (code "132") (name "Net-(LED52-A)") (class "Default")
      (node (ref "LED52") (pin "1") (pinfunction "A_1") (pintype "passive"))
      (node (ref "R52") (pin "2") (pinfunction "2_2") (pintype "passive"))
    )
    (net (code "133") (name "Net-(LED53-A)") (class "Default")
      (node (ref "LED53") (pin "1") (pinfunction "A_1") (pintype "passive"))
      (node (ref "R53") (pin "2") (pinfunction "2_2") (pintype "passive"))
    )
    (net (code "134") (name "Net-(LED54-A)") (class "Default")
      (node (ref "LED54") (pin "1") (pinfunction "A_1") (pintype "passive"))
      (node (ref "R54") (pin "2") (pinfunction "2_2") (pintype "passive"))
    )
    (net (code "135") (name "Net-(LED55-A)") (class "Default")
      (node (ref "LED55") (pin "1") (pinfunction "A_1") (pintype "passive"))
      (node (ref "R55") (pin "2") (pinfunction "2_2") (pintype "passive"))
    )
    (net (code "136") (name "Net-(LED56-A)") (class "Default")
      (node (ref "LED56") (pin "1") (pinfunction "A_1") (pintype "passive"))
      (node (ref "R56") (pin "2") (pinfunction "2_2") (pintype "passive"))
    )
    (net (code "137") (name "Net-(LED57-A)") (class "Default")
      (node (ref "LED57") (pin "1") (pinfunction "A_1") (pintype "passive"))
      (node (ref "R57") (pin "2") (pinfunction "2_2") (pintype "passive"))
    )
    (net (code "138") (name "Net-(LED58-A)") (class "Default")
      (node (ref "LED58") (pin "1") (pinfunction "A_1") (pintype "passive"))
      (node (ref "R58") (pin "2") (pinfunction "2_2") (pintype "passive"))
    )
    (net (code "139") (name "Net-(LED59-A)") (class "Default")
      (node (ref "LED59") (pin "1") (pinfunction "A_1") (pintype "passive"))
      (node (ref "R59") (pin "2") (pinfunction "2_2") (pintype "passive"))
    )
    (net (code "140") (name "Net-(LED60-A)") (class "Default")
      (node (ref "LED60") (pin "1") (pinfunction "A_1") (pintype "passive"))
      (node (ref "R60") (pin "2") (pinfunction "2_2") (pintype "passive"))
    )
    (net (code "141") (name "Net-(LED62-A)") (class "Default")
      (node (ref "LED62") (pin "1") (pinfunction "A_1") (pintype "passive"))
      (node (ref "R62") (pin "2") (pinfunction "2_2") (pintype "passive"))
    )
    (net (code "142") (name "Net-(LED63-A)") (class "Default")
      (node (ref "LED63") (pin "1") (pinfunction "A_1") (pintype "passive"))
      (node (ref "R63") (pin "2") (pinfunction "2_2") (pintype "passive"))
    )
    (net (code "143") (name "Net-(LED64-A)") (class "Default")
      (node (ref "LED64") (pin "1") (pinfunction "A_1") (pintype "passive"))
      (node (ref "R64") (pin "2") (pinfunction "2_2") (pintype "passive"))
    )
    (net (code "144") (name "Net-(LED65-A)") (class "Default")
      (node (ref "LED65") (pin "1") (pinfunction "A_1") (pintype "passive"))
      (node (ref "R65") (pin "2") (pinfunction "2_2") (pintype "passive"))
    )
    (net (code "145") (name "Net-(LED66-A)") (class "Default")
      (node (ref "LED66") (pin "1") (pinfunction "A_1") (pintype "passive"))
      (node (ref "R66") (pin "2") (pinfunction "2_2") (pintype "passive"))
    )
    (net (code "146") (name "Net-(LED67-A)") (class "Default")
      (node (ref "LED67") (pin "1") (pinfunction "A_1") (pintype "passive"))
      (node (ref "R67") (pin "2") (pinfunction "2_2") (pintype "passive"))
    )
    (net (code "147") (name "Net-(LED68-A)") (class "Default")
      (node (ref "LED68") (pin "1") (pinfunction "A_1") (pintype "passive"))
      (node (ref "R68") (pin "2") (pinfunction "2_2") (pintype "passive"))
    )
    (net (code "148") (name "Net-(LED69-A)") (class "Default")
      (node (ref "LED69") (pin "1") (pinfunction "A_1") (pintype "passive"))
      (node (ref "R69") (pin "2") (pinfunction "2_2") (pintype "passive"))
    )
    (net (code "149") (name "Net-(LED70-A)") (class "Default")
      (node (ref "LED70") (pin "1") (pinfunction "A_1") (pintype "passive"))
      (node (ref "R70") (pin "2") (pinfunction "2_2") (pintype "passive"))
    )
    (net (code "150") (name "Net-(LED71-A)") (class "Default")
      (node (ref "LED71") (pin "1") (pinfunction "A_1") (pintype "passive"))
      (node (ref "R71") (pin "2") (pinfunction "2_2") (pintype "passive"))
    )
    (net (code "151") (name "Net-(LED72-A)") (class "Default")
      (node (ref "LED72") (pin "1") (pinfunction "A_1") (pintype "passive"))
      (node (ref "R72") (pin "2") (pinfunction "2_2") (pintype "passive"))
    )
    (net (code "152") (name "Net-(LED73-A)") (class "Default")
      (node (ref "LED73") (pin "1") (pinfunction "A_1") (pintype "passive"))
      (node (ref "R73") (pin "2") (pinfunction "2_2") (pintype "passive"))
    )
    (net (code "153") (name "Net-(LED74-A)") (class "Default")
      (node (ref "LED74") (pin "1") (pinfunction "A_1") (pintype "passive"))
      (node (ref "R74") (pin "2") (pinfunction "2_2") (pintype "passive"))
    )
    (net (code "154") (name "Net-(LED75-A)") (class "Default")
      (node (ref "LED75") (pin "1") (pinfunction "A_1") (pintype "passive"))
      (node (ref "R75") (pin "2") (pinfunction "2_2") (pintype "passive"))
    )
    (net (code "155") (name "Net-(LED76-A)") (class "Default")
      (node (ref "LED76") (pin "1") (pinfunction "A_1") (pintype "passive"))
      (node (ref "R76") (pin "2") (pinfunction "2_2") (pintype "passive"))
    )
    (net (code "156") (name "Net-(LED77-A)") (class "Default")
      (node (ref "LED77") (pin "1") (pinfunction "A_1") (pintype "passive"))
      (node (ref "R77") (pin "2") (pinfunction "2_2") (pintype "passive"))
    )
    (net (code "157") (name "Net-(LED78-A)") (class "Default")
      (node (ref "LED78") (pin "1") (pinfunction "A_1") (pintype "passive"))
      (node (ref "R78") (pin "2") (pinfunction "2_2") (pintype "passive"))
    )
    (net (code "158") (name "Net-(LED79-A)") (class "Default")
      (node (ref "LED79") (pin "1") (pinfunction "A_1") (pintype "passive"))
      (node (ref "R79") (pin "2") (pinfunction "2_2") (pintype "passive"))
    )
    (net (code "159") (name "Net-(LED80-A)") (class "Default")
      (node (ref "LED80") (pin "1") (pinfunction "A_1") (pintype "passive"))
      (node (ref "R80") (pin "2") (pinfunction "2_2") (pintype "passive"))
    )
  )
)
